# carrier_board.net
KiCad netlist of a schematic drawn in EAGLE
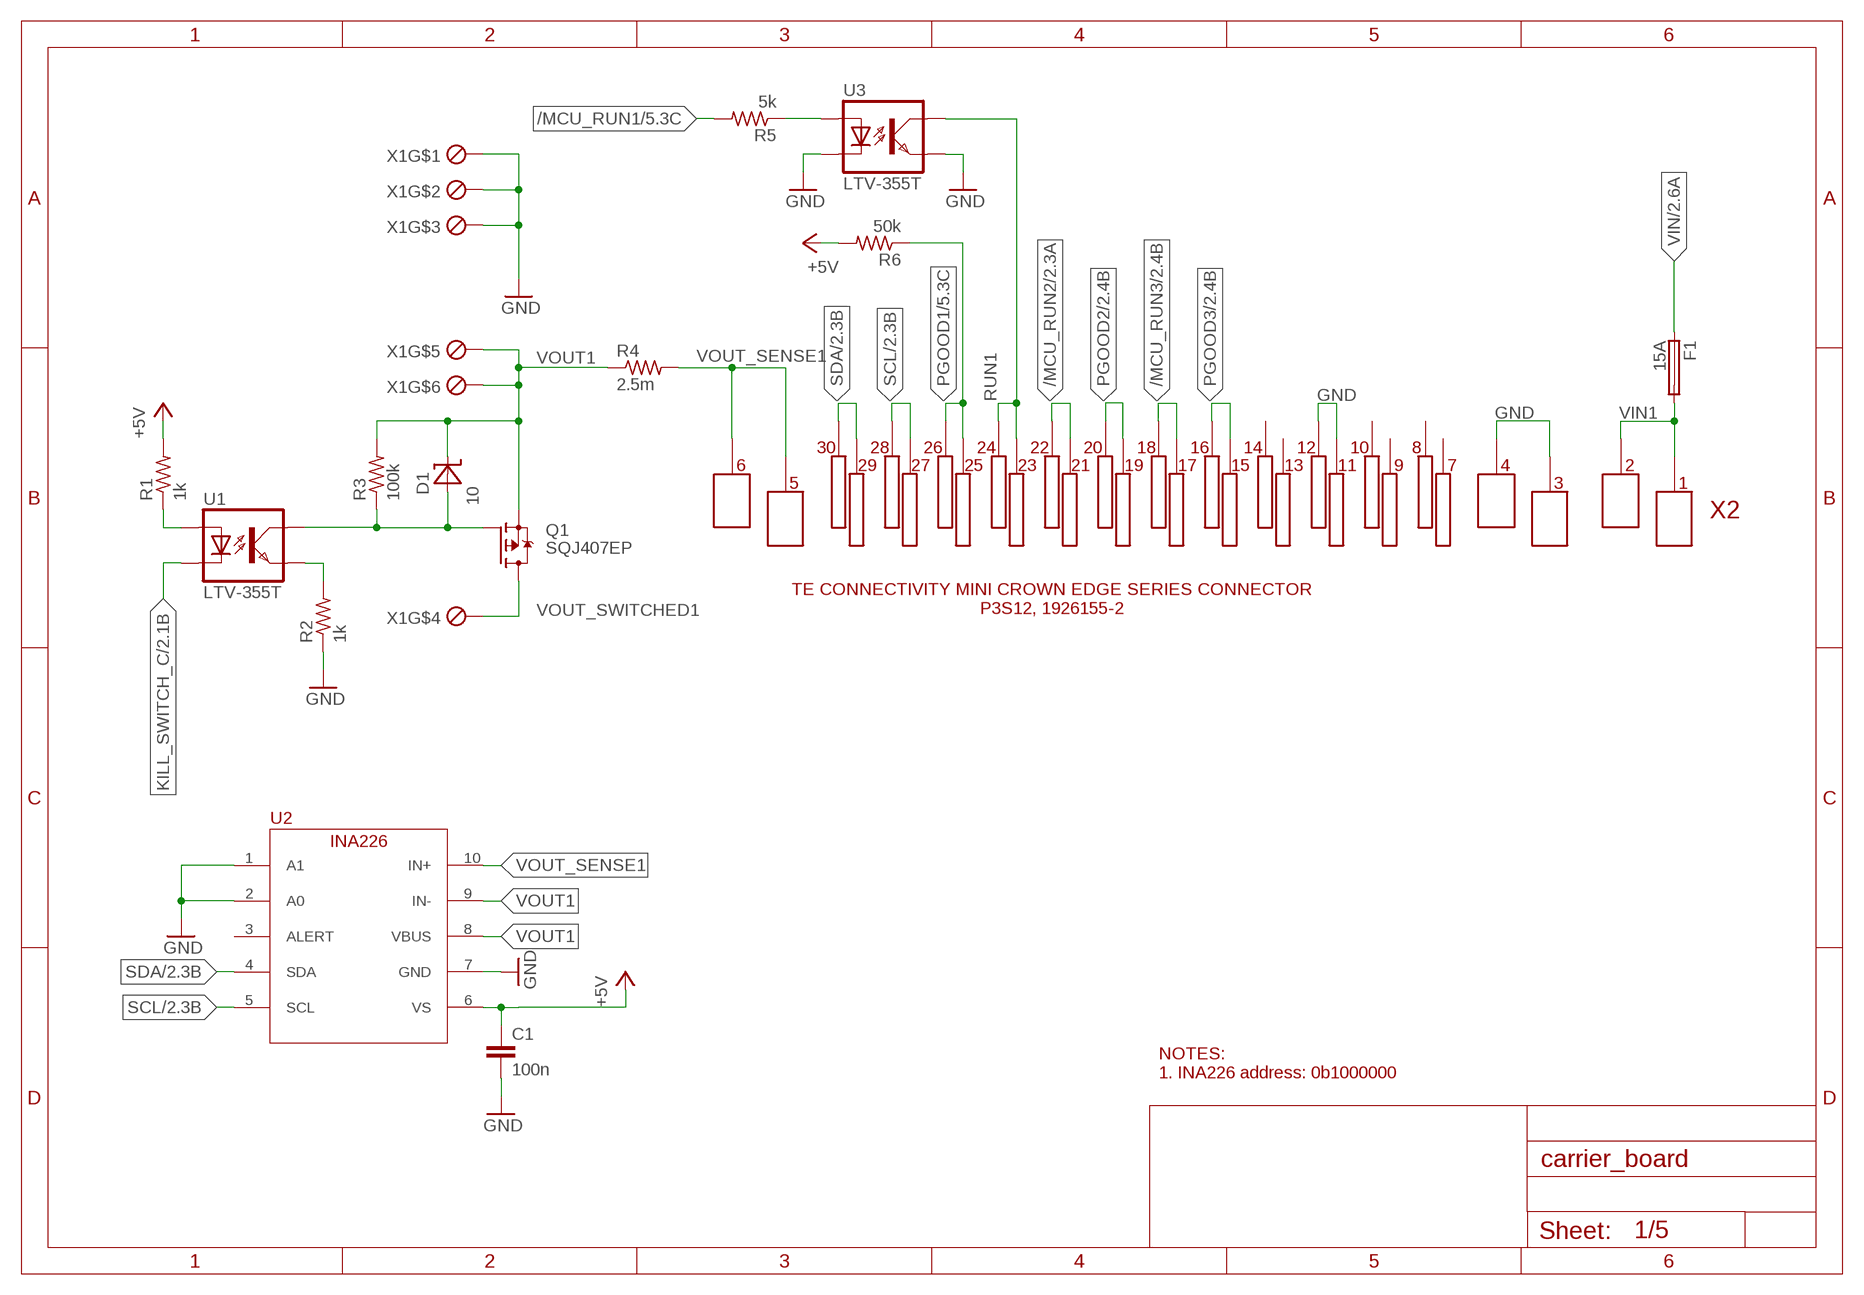
[diagram p0: schematic, sheet 1]
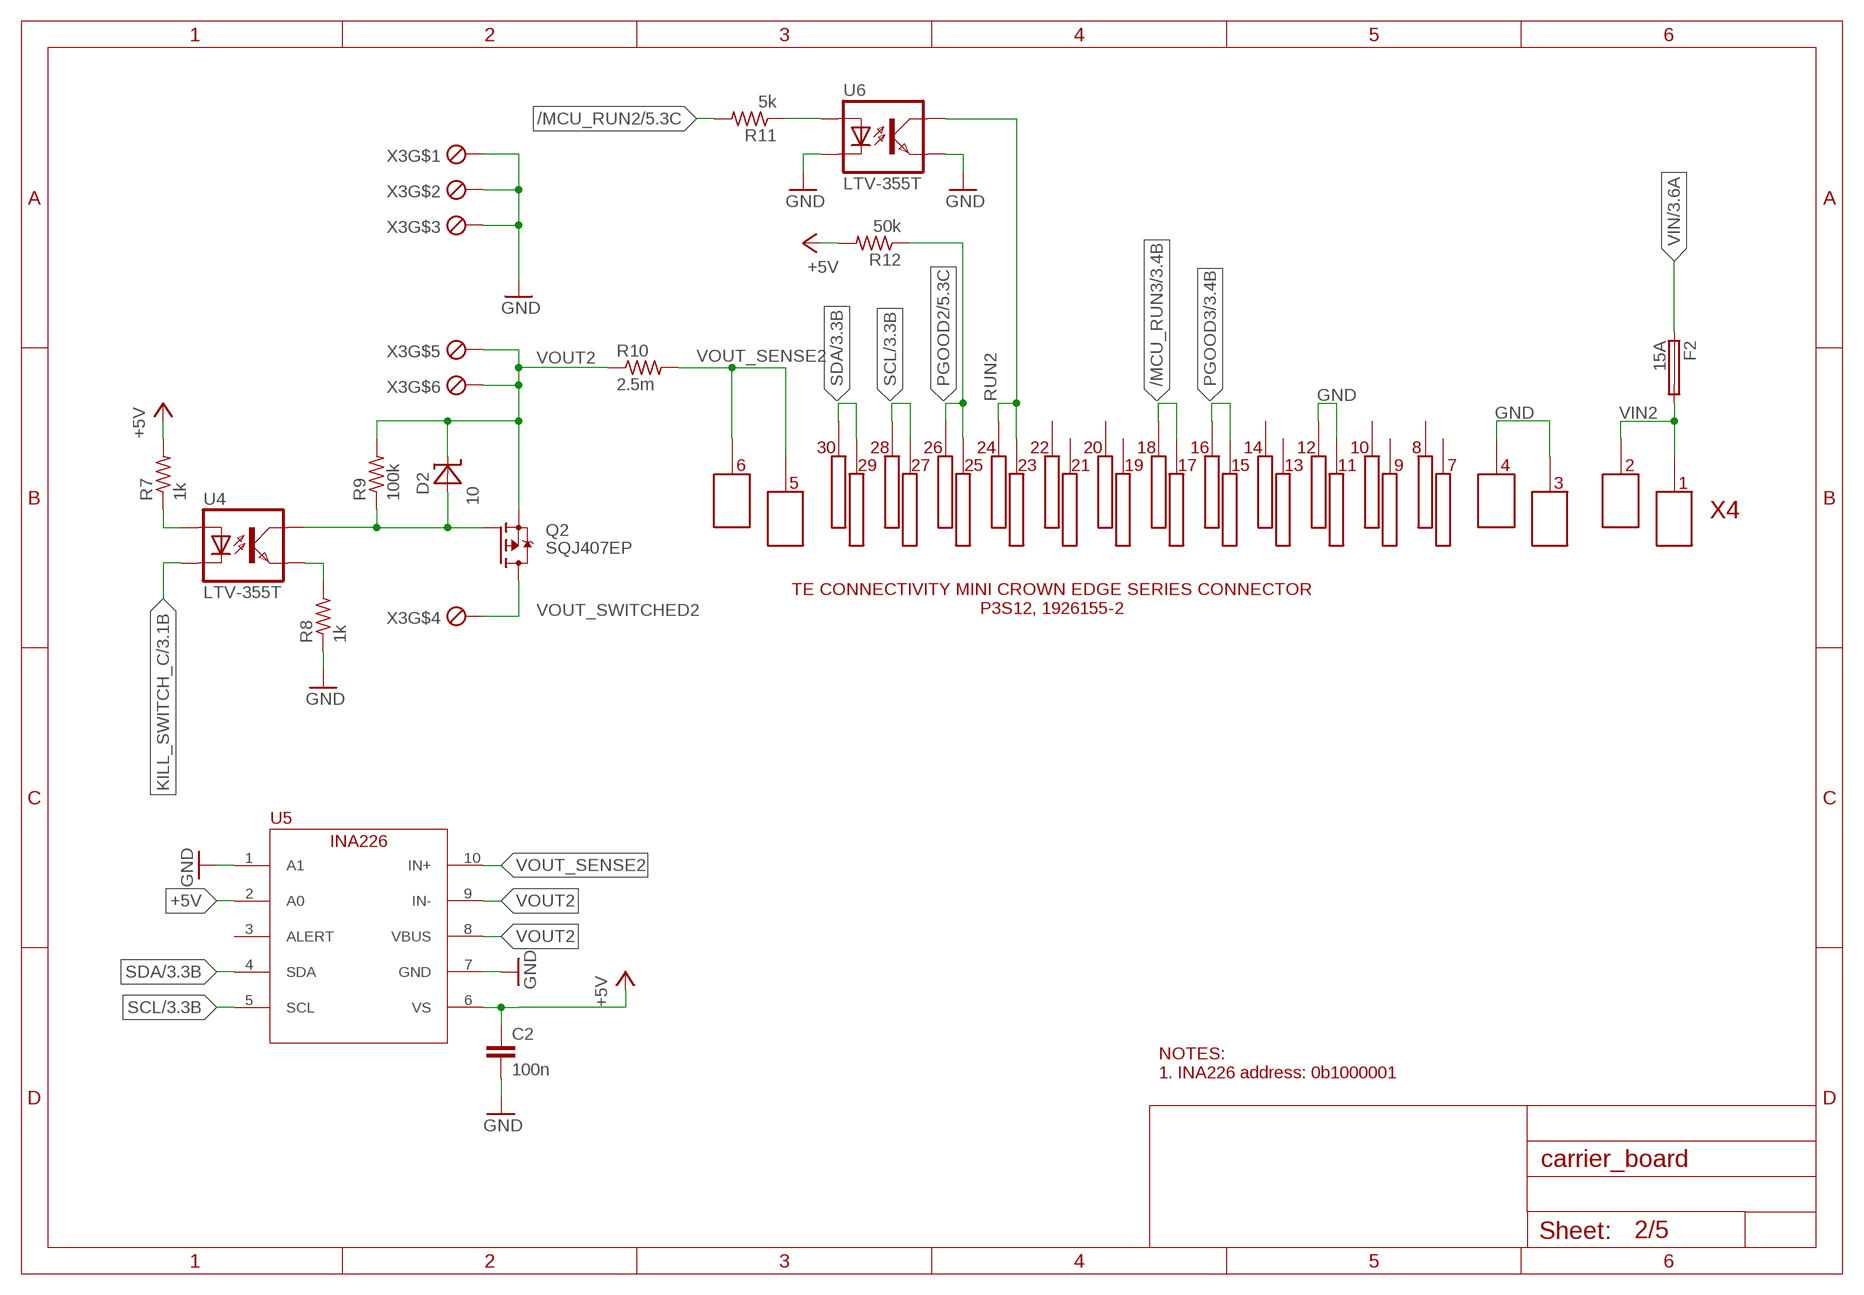
[diagram p1: schematic, sheet 2]
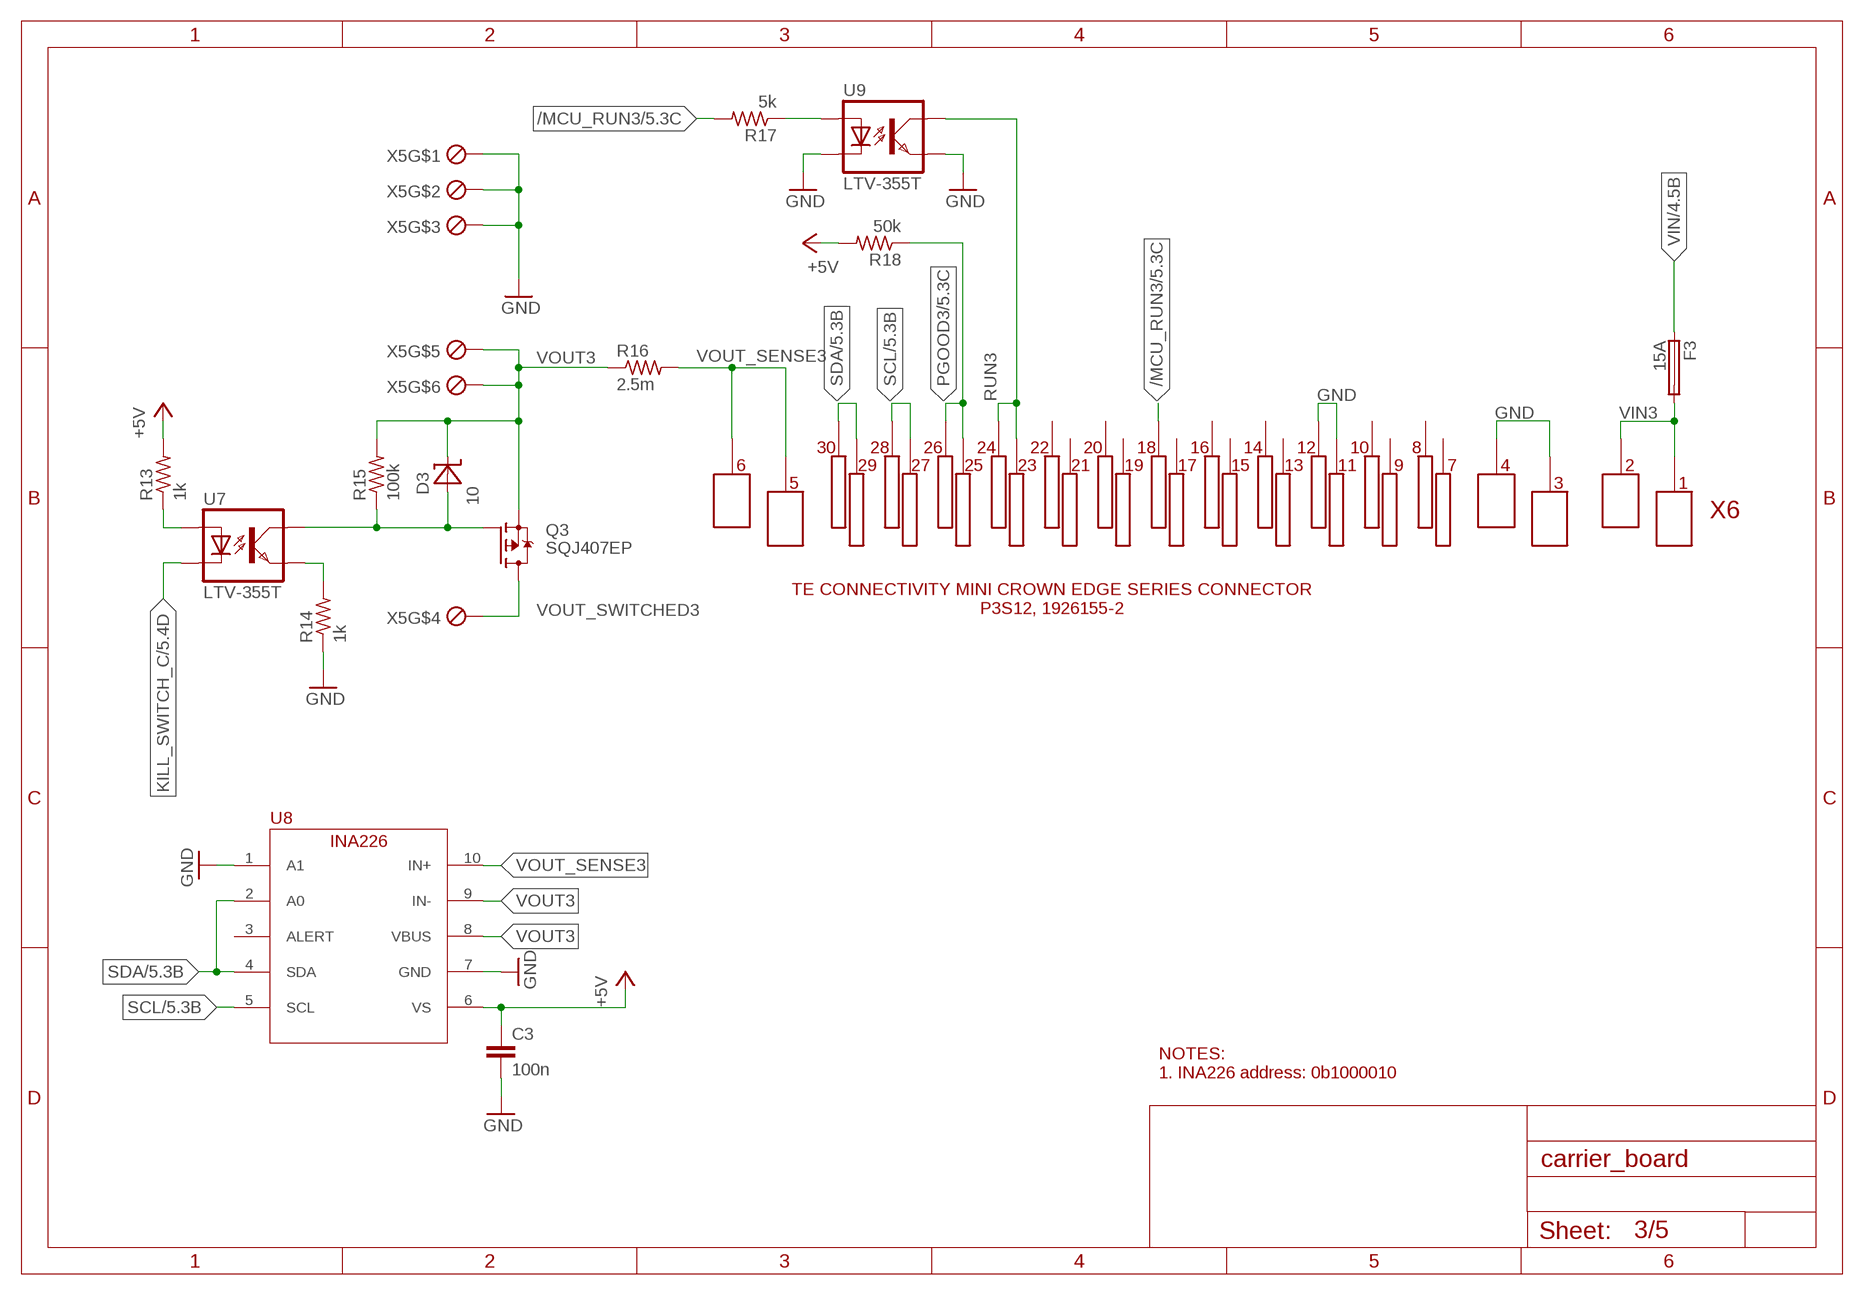
[diagram p2: schematic, sheet 3]
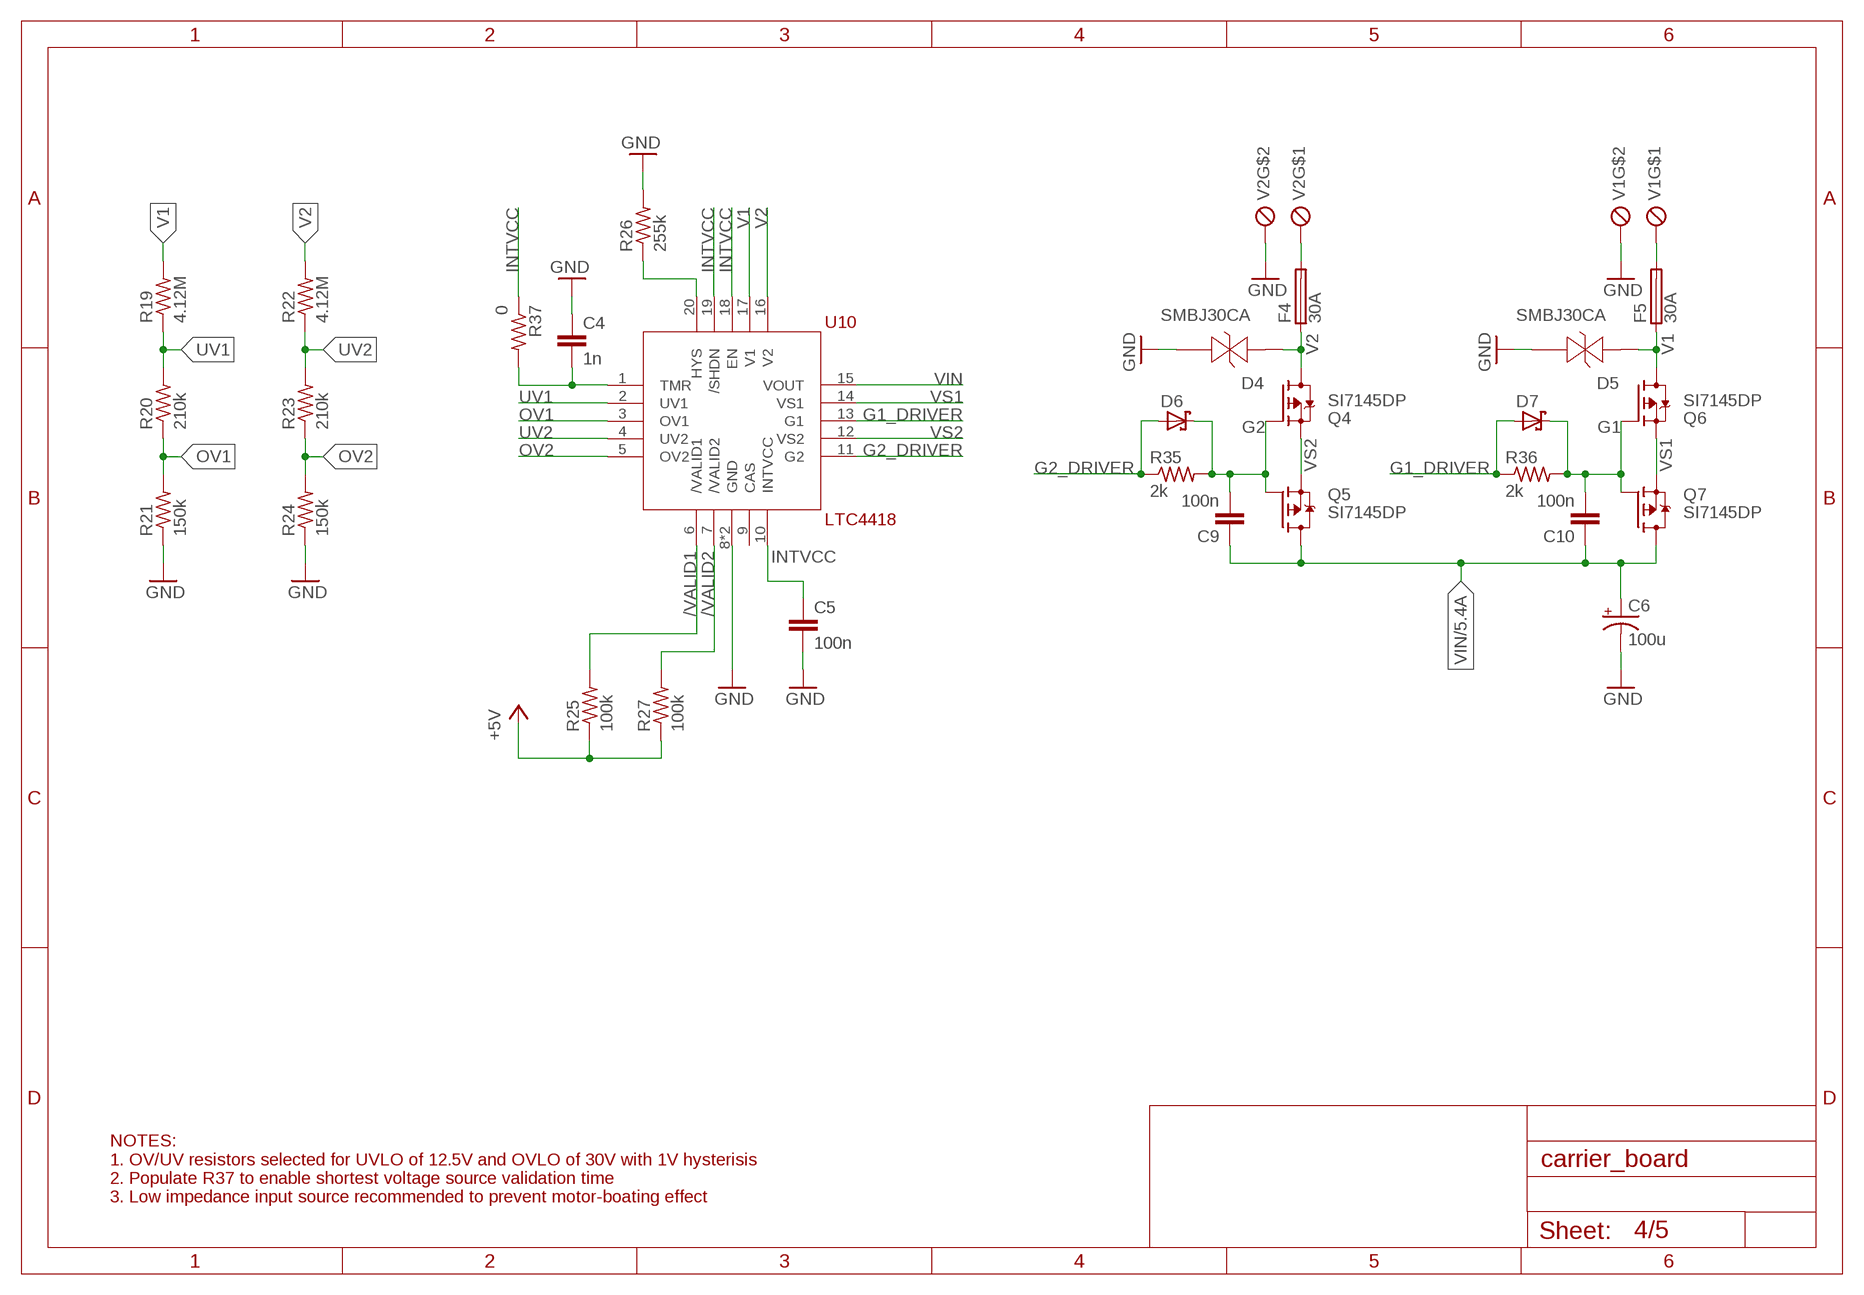
[diagram p3: schematic, sheet 4]
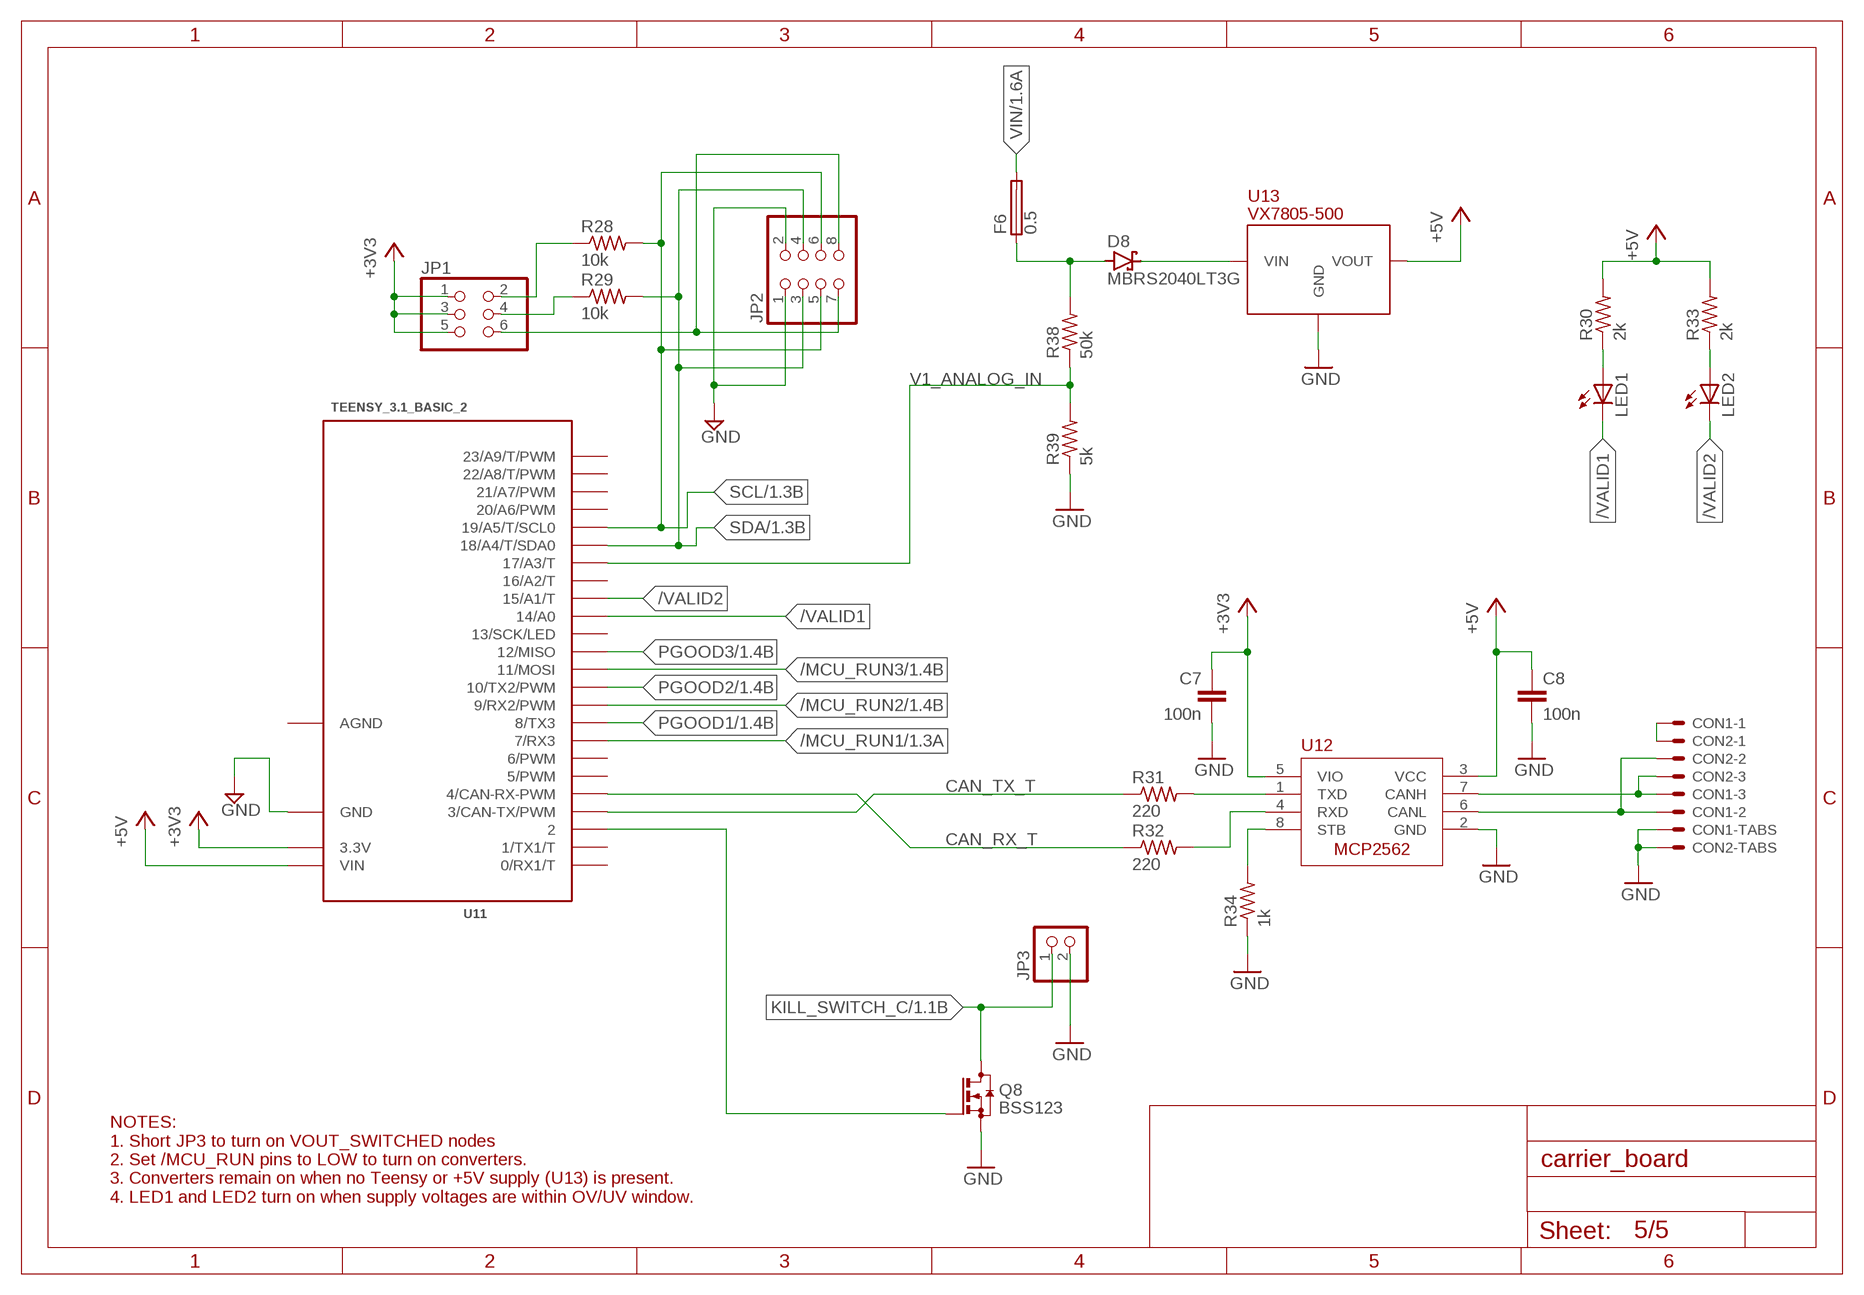
[diagram p4: schematic, sheet 5]

(export (version "E")
  (design (tool "Eeschema 10.0.6"))
  (components
    (comp (ref "C2")
      (value "100n")
      (footprint "eagle-import:C0603")
      (libsource (lib "eagle-import") (part "C-EUC0603"))
    )
    (comp (ref "D2")
      (value "10")
      (footprint "eagle-import:SOD123")
      (libsource (lib "eagle-import") (part "BZT52C10-TP"))
    )
    (comp (ref "F2")
      (value "15A")
      (footprint "eagle-import:3557-10")
      (libsource (lib "eagle-import") (part "3557-10"))
    )
    (comp (ref "Q2")
      (value "SQJ407EP")
      (footprint "eagle-import:POWERPAK_SO8L_SINGLE")
      (libsource (lib "eagle-import") (part "SQJ407EP"))
    )
    (comp (ref "R7")
      (value "1k")
      (footprint "eagle-import:R0603")
      (libsource (lib "eagle-import") (part "R-US_R0603"))
    )
    (comp (ref "R8")
      (value "1k")
      (footprint "eagle-import:R0603")
      (libsource (lib "eagle-import") (part "R-US_R0603"))
    )
    (comp (ref "R9")
      (value "100k")
      (footprint "eagle-import:R0603")
      (libsource (lib "eagle-import") (part "R-US_R0603"))
    )
    (comp (ref "R10")
      (value "2.5m")
      (footprint "eagle-import:R2512")
      (libsource (lib "eagle-import") (part "R-US_R2512"))
    )
    (comp (ref "R11")
      (value "5k")
      (footprint "eagle-import:R0603")
      (libsource (lib "eagle-import") (part "R-US_R0603"))
    )
    (comp (ref "R12")
      (value "50k")
      (footprint "eagle-import:R0603")
      (libsource (lib "eagle-import") (part "R-US_R0603"))
    )
    (comp (ref "U4")
      (value "LTV-355T")
      (footprint "eagle-import:SMD4")
      (libsource (lib "eagle-import") (part "LTV-355T"))
    )
    (comp (ref "U5")
      (value "INA226")
      (footprint "eagle-import:MSOP10")
      (libsource (lib "eagle-import") (part "INA226"))
    )
    (comp (ref "U6")
      (value "LTV-355T")
      (footprint "eagle-import:SMD4")
      (libsource (lib "eagle-import") (part "LTV-355T"))
    )
    (comp (ref "X3")
      (value "284391-6")
      (footprint "eagle-import:284391-6")
      (libsource (lib "eagle-import") (part "284391-6"))
    )
    (comp (ref "X4")
      (value "1926155-2_SOCK")
      (footprint "eagle-import:1926155-2_SOCK")
      (libsource (lib "eagle-import") (part "1926155-2_SOCK"))
    )
    (comp (ref "C4")
      (value "1n")
      (footprint "eagle-import:C0402")
      (libsource (lib "eagle-import") (part "C-EUC0402"))
    )
    (comp (ref "C5")
      (value "100n")
      (footprint "eagle-import:C0402")
      (libsource (lib "eagle-import") (part "C-EUC0402"))
    )
    (comp (ref "C6")
      (value "100u")
      (footprint "eagle-import:E5-10,5")
      (libsource (lib "eagle-import") (part "CPOL-USE5-10.5"))
    )
    (comp (ref "C9")
      (value "100n")
      (footprint "eagle-import:C0603")
      (libsource (lib "eagle-import") (part "C-EUC0603"))
    )
    (comp (ref "C10")
      (value "100n")
      (footprint "eagle-import:C0603")
      (libsource (lib "eagle-import") (part "C-EUC0603"))
    )
    (comp (ref "D4")
      (value "SMBJ30CA")
      (footprint "eagle-import:DO214AA")
      (libsource (lib "eagle-import") (part "SMBJ30CA"))
    )
    (comp (ref "D5")
      (value "SMBJ30CA")
      (footprint "eagle-import:DO214AA")
      (libsource (lib "eagle-import") (part "SMBJ30CA"))
    )
    (comp (ref "D6")
      (value "SD0603S040S0R2")
      (footprint "eagle-import:CHIPLED_0603")
      (libsource (lib "eagle-import") (part "SD0603S040S0R2"))
    )
    (comp (ref "D7")
      (value "SD0603S040S0R2")
      (footprint "eagle-import:CHIPLED_0603")
      (libsource (lib "eagle-import") (part "SD0603S040S0R2"))
    )
    (comp (ref "F4")
      (value "30A")
      (footprint "eagle-import:3557-10")
      (libsource (lib "eagle-import") (part "3557-10"))
    )
    (comp (ref "F5")
      (value "30A")
      (footprint "eagle-import:3557-10")
      (libsource (lib "eagle-import") (part "3557-10"))
    )
    (comp (ref "Q4")
      (value "SI7145DP")
      (footprint "eagle-import:SO-8-POWERPAK")
      (libsource (lib "eagle-import") (part "SI7145"))
    )
    (comp (ref "Q5")
      (value "SI7145DP")
      (footprint "eagle-import:SO-8-POWERPAK")
      (libsource (lib "eagle-import") (part "SI7145"))
    )
    (comp (ref "Q6")
      (value "SI7145DP")
      (footprint "eagle-import:SO-8-POWERPAK")
      (libsource (lib "eagle-import") (part "SI7145"))
    )
    (comp (ref "Q7")
      (value "SI7145DP")
      (footprint "eagle-import:SO-8-POWERPAK")
      (libsource (lib "eagle-import") (part "SI7145"))
    )
    (comp (ref "R19")
      (value "4.12M")
      (footprint "eagle-import:R0402")
      (libsource (lib "eagle-import") (part "R-US_R0402"))
    )
    (comp (ref "R20")
      (value "210k")
      (footprint "eagle-import:R0402")
      (libsource (lib "eagle-import") (part "R-US_R0402"))
    )
    (comp (ref "R21")
      (value "150k")
      (footprint "eagle-import:R0402")
      (libsource (lib "eagle-import") (part "R-US_R0402"))
    )
    (comp (ref "R22")
      (value "4.12M")
      (footprint "eagle-import:R0402")
      (libsource (lib "eagle-import") (part "R-US_R0402"))
    )
    (comp (ref "R23")
      (value "210k")
      (footprint "eagle-import:R0402")
      (libsource (lib "eagle-import") (part "R-US_R0402"))
    )
    (comp (ref "R24")
      (value "150k")
      (footprint "eagle-import:R0402")
      (libsource (lib "eagle-import") (part "R-US_R0402"))
    )
    (comp (ref "R25")
      (value "100k")
      (footprint "eagle-import:R0603")
      (libsource (lib "eagle-import") (part "R-US_R0603"))
    )
    (comp (ref "R26")
      (value "255k")
      (footprint "eagle-import:R0402")
      (libsource (lib "eagle-import") (part "R-US_R0402"))
    )
    (comp (ref "R27")
      (value "100k")
      (footprint "eagle-import:R0603")
      (libsource (lib "eagle-import") (part "R-US_R0603"))
    )
    (comp (ref "R35")
      (value "2k")
      (footprint "eagle-import:R0603")
      (libsource (lib "eagle-import") (part "R-US_R0603"))
    )
    (comp (ref "R36")
      (value "2k")
      (footprint "eagle-import:R0603")
      (libsource (lib "eagle-import") (part "R-US_R0603"))
    )
    (comp (ref "R37")
      (value "0")
      (footprint "eagle-import:R0402")
      (libsource (lib "eagle-import") (part "R-US_R0402"))
    )
    (comp (ref "U10")
      (value "LTC4418")
      (footprint "eagle-import:QFN20")
      (libsource (lib "eagle-import") (part "LTC4418"))
    )
    (comp (ref "V1")
      (value "MKDSD_1730502")
      (footprint "eagle-import:MKDSD_1730502")
      (libsource (lib "eagle-import") (part "MKDSD_1730502"))
    )
    (comp (ref "V2")
      (value "MKDSD_1730502")
      (footprint "eagle-import:MKDSD_1730502")
      (libsource (lib "eagle-import") (part "MKDSD_1730502"))
    )
    (comp (ref "C3")
      (value "100n")
      (footprint "eagle-import:C0603")
      (libsource (lib "eagle-import") (part "C-EUC0603"))
    )
    (comp (ref "D3")
      (value "10")
      (footprint "eagle-import:SOD123")
      (libsource (lib "eagle-import") (part "BZT52C10-TP"))
    )
    (comp (ref "F3")
      (value "15A")
      (footprint "eagle-import:3557-10")
      (libsource (lib "eagle-import") (part "3557-10"))
    )
    (comp (ref "Q3")
      (value "SQJ407EP")
      (footprint "eagle-import:POWERPAK_SO8L_SINGLE")
      (libsource (lib "eagle-import") (part "SQJ407EP"))
    )
    (comp (ref "R13")
      (value "1k")
      (footprint "eagle-import:R0603")
      (libsource (lib "eagle-import") (part "R-US_R0603"))
    )
    (comp (ref "R14")
      (value "1k")
      (footprint "eagle-import:R0603")
      (libsource (lib "eagle-import") (part "R-US_R0603"))
    )
    (comp (ref "R15")
      (value "100k")
      (footprint "eagle-import:R0603")
      (libsource (lib "eagle-import") (part "R-US_R0603"))
    )
    (comp (ref "R16")
      (value "2.5m")
      (footprint "eagle-import:R2512")
      (libsource (lib "eagle-import") (part "R-US_R2512"))
    )
    (comp (ref "R17")
      (value "5k")
      (footprint "eagle-import:R0603")
      (libsource (lib "eagle-import") (part "R-US_R0603"))
    )
    (comp (ref "R18")
      (value "50k")
      (footprint "eagle-import:R0603")
      (libsource (lib "eagle-import") (part "R-US_R0603"))
    )
    (comp (ref "U7")
      (value "LTV-355T")
      (footprint "eagle-import:SMD4")
      (libsource (lib "eagle-import") (part "LTV-355T"))
    )
    (comp (ref "U8")
      (value "INA226")
      (footprint "eagle-import:MSOP10")
      (libsource (lib "eagle-import") (part "INA226"))
    )
    (comp (ref "U9")
      (value "LTV-355T")
      (footprint "eagle-import:SMD4")
      (libsource (lib "eagle-import") (part "LTV-355T"))
    )
    (comp (ref "X5")
      (value "284391-6")
      (footprint "eagle-import:284391-6")
      (libsource (lib "eagle-import") (part "284391-6"))
    )
    (comp (ref "X6")
      (value "1926155-2_SOCK")
      (footprint "eagle-import:1926155-2_SOCK")
      (libsource (lib "eagle-import") (part "1926155-2_SOCK"))
    )
    (comp (ref "C1")
      (value "100n")
      (footprint "eagle-import:C0603")
      (libsource (lib "eagle-import") (part "C-EUC0603"))
    )
    (comp (ref "D1")
      (value "10")
      (footprint "eagle-import:SOD123")
      (libsource (lib "eagle-import") (part "BZT52C10-TP"))
    )
    (comp (ref "F1")
      (value "15A")
      (footprint "eagle-import:3557-10")
      (libsource (lib "eagle-import") (part "3557-10"))
    )
    (comp (ref "Q1")
      (value "SQJ407EP")
      (footprint "eagle-import:POWERPAK_SO8L_SINGLE")
      (libsource (lib "eagle-import") (part "SQJ407EP"))
    )
    (comp (ref "R1")
      (value "1k")
      (footprint "eagle-import:R0603")
      (libsource (lib "eagle-import") (part "R-US_R0603"))
    )
    (comp (ref "R2")
      (value "1k")
      (footprint "eagle-import:R0603")
      (libsource (lib "eagle-import") (part "R-US_R0603"))
    )
    (comp (ref "R3")
      (value "100k")
      (footprint "eagle-import:R0603")
      (libsource (lib "eagle-import") (part "R-US_R0603"))
    )
    (comp (ref "R4")
      (value "2.5m")
      (footprint "eagle-import:R2512")
      (libsource (lib "eagle-import") (part "R-US_R2512"))
    )
    (comp (ref "R5")
      (value "5k")
      (footprint "eagle-import:R0603")
      (libsource (lib "eagle-import") (part "R-US_R0603"))
    )
    (comp (ref "R6")
      (value "50k")
      (footprint "eagle-import:R0603")
      (libsource (lib "eagle-import") (part "R-US_R0603"))
    )
    (comp (ref "U1")
      (value "LTV-355T")
      (footprint "eagle-import:SMD4")
      (libsource (lib "eagle-import") (part "LTV-355T"))
    )
    (comp (ref "U2")
      (value "INA226")
      (footprint "eagle-import:MSOP10")
      (libsource (lib "eagle-import") (part "INA226"))
    )
    (comp (ref "U3")
      (value "LTV-355T")
      (footprint "eagle-import:SMD4")
      (libsource (lib "eagle-import") (part "LTV-355T"))
    )
    (comp (ref "X1")
      (value "284391-6")
      (footprint "eagle-import:284391-6")
      (libsource (lib "eagle-import") (part "284391-6"))
    )
    (comp (ref "X2")
      (value "1926155-2_SOCK")
      (footprint "eagle-import:1926155-2_SOCK")
      (libsource (lib "eagle-import") (part "1926155-2_SOCK"))
    )
    (comp (ref "C7")
      (value "100n")
      (footprint "eagle-import:C0805")
      (libsource (lib "eagle-import") (part "C-EUC0805"))
    )
    (comp (ref "C8")
      (value "100n")
      (footprint "eagle-import:C0805")
      (libsource (lib "eagle-import") (part "C-EUC0805"))
    )
    (comp (ref "CON1")
      (value "SM03B-GHS-TB")
      (footprint "eagle-import:SM03B-GHS-TB")
      (libsource (lib "eagle-import") (part "SM03B-GHS-TB"))
    )
    (comp (ref "CON2")
      (value "SM03B-GHS-TB")
      (footprint "eagle-import:SM03B-GHS-TB")
      (libsource (lib "eagle-import") (part "SM03B-GHS-TB"))
    )
    (comp (ref "D8")
      (value "MBRS2040LT3G")
      (footprint "eagle-import:SMB")
      (libsource (lib "eagle-import") (part "MBRS130LT3"))
    )
    (comp (ref "F6")
      (value "0.5")
      (footprint "eagle-import:R1206")
      (libsource (lib "eagle-import") (part "501_FUSE"))
    )
    (comp (ref "JP1")
      (value "PINHD-2X3")
      (footprint "eagle-import:2X03")
      (libsource (lib "eagle-import") (part "PINHD-2X3"))
    )
    (comp (ref "JP2")
      (value "PINHD-2X4")
      (footprint "eagle-import:2X04")
      (libsource (lib "eagle-import") (part "PINHD-2X4"))
    )
    (comp (ref "JP3")
      (value "PINHD-1X02_2.54-SMD-90°")
      (footprint "eagle-import:1X02SMD_90")
      (libsource (lib "eagle-import") (part "PINHD-1X02_2.54-SMD-90°"))
    )
    (comp (ref "LED1")
      (value "LEDCHIPLED_0603")
      (footprint "eagle-import:CHIPLED_0603")
      (libsource (lib "eagle-import") (part "LEDCHIPLED_0603"))
    )
    (comp (ref "LED2")
      (value "LEDCHIPLED_0603")
      (footprint "eagle-import:CHIPLED_0603")
      (libsource (lib "eagle-import") (part "LEDCHIPLED_0603"))
    )
    (comp (ref "Q8")
      (value "BSS123")
      (footprint "eagle-import:SOT23")
      (libsource (lib "eagle-import") (part "BSS123"))
    )
    (comp (ref "R28")
      (value "10k")
      (footprint "eagle-import:R0805")
      (libsource (lib "eagle-import") (part "R-US_R0805"))
    )
    (comp (ref "R29")
      (value "10k")
      (footprint "eagle-import:R0805")
      (libsource (lib "eagle-import") (part "R-US_R0805"))
    )
    (comp (ref "R30")
      (value "2k")
      (footprint "eagle-import:R0603")
      (libsource (lib "eagle-import") (part "R-US_R0603"))
    )
    (comp (ref "R31")
      (value "220")
      (footprint "eagle-import:R0805")
      (libsource (lib "eagle-import") (part "R-US_R0805"))
    )
    (comp (ref "R32")
      (value "220")
      (footprint "eagle-import:R0805")
      (libsource (lib "eagle-import") (part "R-US_R0805"))
    )
    (comp (ref "R33")
      (value "2k")
      (footprint "eagle-import:R0603")
      (libsource (lib "eagle-import") (part "R-US_R0603"))
    )
    (comp (ref "R34")
      (value "1k")
      (footprint "eagle-import:R0805")
      (libsource (lib "eagle-import") (part "R-US_R0805"))
    )
    (comp (ref "R38")
      (value "50k")
      (footprint "eagle-import:R0603")
      (libsource (lib "eagle-import") (part "R-US_R0603"))
    )
    (comp (ref "R39")
      (value "5k")
      (footprint "eagle-import:R0603")
      (libsource (lib "eagle-import") (part "R-US_R0603"))
    )
    (comp (ref "U11")
      (value "TEENSY_3.1_BASIC_2")
      (footprint "eagle-import:TEENSY_3.1_BASIC_2")
      (libsource (lib "eagle-import") (part "TEENSY_3.1_BASIC_2"))
    )
    (comp (ref "U12")
      (value "MCP2562")
      (footprint "eagle-import:SO-8")
      (libsource (lib "eagle-import") (part "MCP2562"))
    )
    (comp (ref "U13")
      (value "VX7805-500")
      (footprint "eagle-import:0.1__LINEAR_REGULATOR_REPLACEMENT")
      (libsource (lib "eagle-import") (part "0.1{dblquote}_LINEAR_REGULATOR_REPLACEMENT"))
    )
  )
  (nets
    (net (code "1") (name "+3V3") (class "Default")
      (node (ref "C7") (pin "1") (pinfunction "1_1") (pintype "passive"))
      (node (ref "JP1") (pin "1") (pinfunction "1_1") (pintype "passive"))
      (node (ref "JP1") (pin "3") (pinfunction "3_3") (pintype "passive"))
      (node (ref "JP1") (pin "5") (pinfunction "5_5") (pintype "passive"))
      (node (ref "U11") (pin "3.3V") (pinfunction "3.3V_3.3V") (pintype "power_in"))
      (node (ref "U12") (pin "5") (pinfunction "VIO_5") (pintype "bidirectional"))
    )
    (net (code "2") (name "+5V") (class "Default")
      (node (ref "C1") (pin "1") (pinfunction "1_1") (pintype "passive"))
      (node (ref "C2") (pin "1") (pinfunction "1_1") (pintype "passive"))
      (node (ref "C3") (pin "1") (pinfunction "1_1") (pintype "passive"))
      (node (ref "C8") (pin "1") (pinfunction "1_1") (pintype "passive"))
      (node (ref "R1") (pin "2") (pinfunction "2_2") (pintype "passive"))
      (node (ref "R12") (pin "2") (pinfunction "2_2") (pintype "passive"))
      (node (ref "R13") (pin "2") (pinfunction "2_2") (pintype "passive"))
      (node (ref "R18") (pin "2") (pinfunction "2_2") (pintype "passive"))
      (node (ref "R25") (pin "1") (pinfunction "1_1") (pintype "passive"))
      (node (ref "R27") (pin "1") (pinfunction "1_1") (pintype "passive"))
      (node (ref "R30") (pin "2") (pinfunction "2_2") (pintype "passive"))
      (node (ref "R33") (pin "2") (pinfunction "2_2") (pintype "passive"))
      (node (ref "R6") (pin "2") (pinfunction "2_2") (pintype "passive"))
      (node (ref "R7") (pin "2") (pinfunction "2_2") (pintype "passive"))
      (node (ref "U11") (pin "VIN") (pinfunction "VIN_VIN") (pintype "power_in"))
      (node (ref "U12") (pin "3") (pinfunction "VCC_3") (pintype "bidirectional"))
      (node (ref "U13") (pin "3") (pinfunction "VOUT_3") (pintype "passive"))
      (node (ref "U2") (pin "6") (pinfunction "VS_6") (pintype "bidirectional"))
      (node (ref "U5") (pin "2") (pinfunction "A0_2") (pintype "bidirectional"))
      (node (ref "U5") (pin "6") (pinfunction "VS_6") (pintype "bidirectional"))
      (node (ref "U8") (pin "6") (pinfunction "VS_6") (pintype "bidirectional"))
    )
    (net (code "3") (name "AGND") (class "Default")
      (node (ref "U11") (pin "AGND") (pinfunction "AGND_AGND") (pintype "power_in"))
    )
    (net (code "4") (name "CAN_RX_T") (class "Default")
      (node (ref "R32") (pin "1") (pinfunction "1_1") (pintype "passive"))
      (node (ref "U11") (pin "4") (pinfunction "4/CAN-RX-PWM_4") (pintype "bidirectional"))
    )
    (net (code "5") (name "CAN_TX_T") (class "Default")
      (node (ref "R31") (pin "1") (pinfunction "1_1") (pintype "passive"))
      (node (ref "U11") (pin "3") (pinfunction "3/CAN-TX/PWM_3") (pintype "bidirectional"))
    )
    (net (code "6") (name "G1") (class "Default")
      (node (ref "C10") (pin "2") (pinfunction "2_2") (pintype "passive"))
      (node (ref "D7") (pin "C") (pinfunction "C_C") (pintype "passive"))
      (node (ref "Q6") (pin "4") (pinfunction "G_4") (pintype "passive"))
      (node (ref "Q7") (pin "4") (pinfunction "G_4") (pintype "passive"))
      (node (ref "R36") (pin "2") (pinfunction "2_2") (pintype "passive"))
    )
    (net (code "7") (name "G1_DRIVER") (class "Default")
      (node (ref "D7") (pin "A") (pinfunction "A_A") (pintype "passive"))
      (node (ref "R36") (pin "1") (pinfunction "1_1") (pintype "passive"))
      (node (ref "U10") (pin "13") (pinfunction "G1_13") (pintype "bidirectional"))
    )
    (net (code "8") (name "G2") (class "Default")
      (node (ref "C9") (pin "2") (pinfunction "2_2") (pintype "passive"))
      (node (ref "D6") (pin "C") (pinfunction "C_C") (pintype "passive"))
      (node (ref "Q4") (pin "4") (pinfunction "G_4") (pintype "passive"))
      (node (ref "Q5") (pin "4") (pinfunction "G_4") (pintype "passive"))
      (node (ref "R35") (pin "2") (pinfunction "2_2") (pintype "passive"))
    )
    (net (code "9") (name "G2_DRIVER") (class "Default")
      (node (ref "D6") (pin "A") (pinfunction "A_A") (pintype "passive"))
      (node (ref "R35") (pin "1") (pinfunction "1_1") (pintype "passive"))
      (node (ref "U10") (pin "11") (pinfunction "G2_11") (pintype "bidirectional"))
    )
    (net (code "10") (name "GND") (class "Default")
      (node (ref "C1") (pin "2") (pinfunction "2_2") (pintype "passive"))
      (node (ref "C2") (pin "2") (pinfunction "2_2") (pintype "passive"))
      (node (ref "C3") (pin "2") (pinfunction "2_2") (pintype "passive"))
      (node (ref "C4") (pin "1") (pinfunction "1_1") (pintype "passive"))
      (node (ref "C5") (pin "2") (pinfunction "2_2") (pintype "passive"))
      (node (ref "C6") (pin "-") (pinfunction "-_-") (pintype "passive"))
      (node (ref "C7") (pin "2") (pinfunction "2_2") (pintype "passive"))
      (node (ref "C8") (pin "2") (pinfunction "2_2") (pintype "passive"))
      (node (ref "CON1") (pin "P$4") (pinfunction "S_P$4") (pintype "passive"))
      (node (ref "CON1") (pin "P$5") (pinfunction "S_P$5") (pintype "passive"))
      (node (ref "CON2") (pin "P$4") (pinfunction "S_P$4") (pintype "passive"))
      (node (ref "CON2") (pin "P$5") (pinfunction "S_P$5") (pintype "passive"))
      (node (ref "D4") (pin "A") (pinfunction "2_A") (pintype "passive"))
      (node (ref "D5") (pin "A") (pinfunction "2_A") (pintype "passive"))
      (node (ref "JP2") (pin "1") (pinfunction "1_1") (pintype "passive"))
      (node (ref "JP2") (pin "2") (pinfunction "2_2") (pintype "passive"))
      (node (ref "JP3") (pin "2") (pinfunction "2_2") (pintype "passive"))
      (node (ref "Q8") (pin "2") (pinfunction "S_2") (pintype "passive"))
      (node (ref "R14") (pin "1") (pinfunction "1_1") (pintype "passive"))
      (node (ref "R2") (pin "1") (pinfunction "1_1") (pintype "passive"))
      (node (ref "R21") (pin "1") (pinfunction "1_1") (pintype "passive"))
      (node (ref "R24") (pin "1") (pinfunction "1_1") (pintype "passive"))
      (node (ref "R26") (pin "2") (pinfunction "2_2") (pintype "passive"))
      (node (ref "R34") (pin "1") (pinfunction "1_1") (pintype "passive"))
      (node (ref "R39") (pin "1") (pinfunction "1_1") (pintype "passive"))
      (node (ref "R8") (pin "1") (pinfunction "1_1") (pintype "passive"))
      (node (ref "U10") (pin "8") (pinfunction "GND_8") (pintype "bidirectional"))
      (node (ref "U10") (pin "EXP") (pinfunction "GND_EXP") (pintype "bidirectional"))
      (node (ref "U11") (pin "GND") (pinfunction "GND_GND") (pintype "power_in"))
      (node (ref "U12") (pin "2") (pinfunction "GND_2") (pintype "bidirectional"))
      (node (ref "U13") (pin "2") (pinfunction "GND_2") (pintype "passive"))
      (node (ref "U2") (pin "1") (pinfunction "A1_1") (pintype "bidirectional"))
      (node (ref "U2") (pin "2") (pinfunction "A0_2") (pintype "bidirectional"))
      (node (ref "U2") (pin "7") (pinfunction "GND_7") (pintype "bidirectional"))
      (node (ref "U3") (pin "CATHODE") (pinfunction "C_CATHODE") (pintype "passive"))
      (node (ref "U3") (pin "EMITTER") (pinfunction "EMIT_EMITTER") (pintype "passive"))
      (node (ref "U5") (pin "1") (pinfunction "A1_1") (pintype "bidirectional"))
      (node (ref "U5") (pin "7") (pinfunction "GND_7") (pintype "bidirectional"))
      (node (ref "U6") (pin "CATHODE") (pinfunction "C_CATHODE") (pintype "passive"))
      (node (ref "U6") (pin "EMITTER") (pinfunction "EMIT_EMITTER") (pintype "passive"))
      (node (ref "U8") (pin "1") (pinfunction "A1_1") (pintype "bidirectional"))
      (node (ref "U8") (pin "7") (pinfunction "GND_7") (pintype "bidirectional"))
      (node (ref "U9") (pin "CATHODE") (pinfunction "C_CATHODE") (pintype "passive"))
      (node (ref "U9") (pin "EMITTER") (pinfunction "EMIT_EMITTER") (pintype "passive"))
      (node (ref "V1") (pin "P$2") (pinfunction "1_P$2") (pintype "passive"))
      (node (ref "V1") (pin "P$4") (pinfunction "1_P$4") (pintype "passive"))
      (node (ref "V2") (pin "P$2") (pinfunction "1_P$2") (pintype "passive"))
      (node (ref "V2") (pin "P$4") (pinfunction "1_P$4") (pintype "passive"))
      (node (ref "X1") (pin "P$1") (pinfunction "1_P$1") (pintype "passive"))
      (node (ref "X1") (pin "P$2") (pinfunction "1_P$2") (pintype "passive"))
      (node (ref "X1") (pin "P$3") (pinfunction "1_P$3") (pintype "passive"))
      (node (ref "X2") (pin "P$11") (pinfunction "P$11_P$11") (pintype "bidirectional"))
      (node (ref "X2") (pin "P$12") (pinfunction "P$12_P$12") (pintype "bidirectional"))
      (node (ref "X2") (pin "P$3_1") (pinfunction "P$3_P$3_1") (pintype "bidirectional"))
      (node (ref "X2") (pin "P$3_2") (pinfunction "P$3_P$3_2") (pintype "bidirectional"))
      (node (ref "X2") (pin "P$3_3") (pinfunction "P$3_P$3_3") (pintype "bidirectional"))
      (node (ref "X2") (pin "P$4_1") (pinfunction "P$4_P$4_1") (pintype "bidirectional"))
      (node (ref "X2") (pin "P$4_2") (pinfunction "P$4_P$4_2") (pintype "bidirectional"))
      (node (ref "X2") (pin "P$4_3") (pinfunction "P$4_P$4_3") (pintype "bidirectional"))
      (node (ref "X3") (pin "P$1") (pinfunction "1_P$1") (pintype "passive"))
      (node (ref "X3") (pin "P$2") (pinfunction "1_P$2") (pintype "passive"))
      (node (ref "X3") (pin "P$3") (pinfunction "1_P$3") (pintype "passive"))
      (node (ref "X4") (pin "P$11") (pinfunction "P$11_P$11") (pintype "bidirectional"))
      (node (ref "X4") (pin "P$12") (pinfunction "P$12_P$12") (pintype "bidirectional"))
      (node (ref "X4") (pin "P$3_1") (pinfunction "P$3_P$3_1") (pintype "bidirectional"))
      (node (ref "X4") (pin "P$3_2") (pinfunction "P$3_P$3_2") (pintype "bidirectional"))
      (node (ref "X4") (pin "P$3_3") (pinfunction "P$3_P$3_3") (pintype "bidirectional"))
      (node (ref "X4") (pin "P$4_1") (pinfunction "P$4_P$4_1") (pintype "bidirectional"))
      (node (ref "X4") (pin "P$4_2") (pinfunction "P$4_P$4_2") (pintype "bidirectional"))
      (node (ref "X4") (pin "P$4_3") (pinfunction "P$4_P$4_3") (pintype "bidirectional"))
      (node (ref "X5") (pin "P$1") (pinfunction "1_P$1") (pintype "passive"))
      (node (ref "X5") (pin "P$2") (pinfunction "1_P$2") (pintype "passive"))
      (node (ref "X5") (pin "P$3") (pinfunction "1_P$3") (pintype "passive"))
      (node (ref "X6") (pin "P$11") (pinfunction "P$11_P$11") (pintype "bidirectional"))
      (node (ref "X6") (pin "P$12") (pinfunction "P$12_P$12") (pintype "bidirectional"))
      (node (ref "X6") (pin "P$3_1") (pinfunction "P$3_P$3_1") (pintype "bidirectional"))
      (node (ref "X6") (pin "P$3_2") (pinfunction "P$3_P$3_2") (pintype "bidirectional"))
      (node (ref "X6") (pin "P$3_3") (pinfunction "P$3_P$3_3") (pintype "bidirectional"))
      (node (ref "X6") (pin "P$4_1") (pinfunction "P$4_P$4_1") (pintype "bidirectional"))
      (node (ref "X6") (pin "P$4_2") (pinfunction "P$4_P$4_2") (pintype "bidirectional"))
      (node (ref "X6") (pin "P$4_3") (pinfunction "P$4_P$4_3") (pintype "bidirectional"))
    )
    (net (code "11") (name "INTVCC") (class "Default")
      (node (ref "C5") (pin "1") (pinfunction "1_1") (pintype "passive"))
      (node (ref "R37") (pin "1") (pinfunction "1_1") (pintype "passive"))
      (node (ref "U10") (pin "10") (pinfunction "INTVCC_10") (pintype "bidirectional"))
      (node (ref "U10") (pin "18") (pinfunction "EN_18") (pintype "bidirectional"))
      (node (ref "U10") (pin "19") (pinfunction "/SHDN_19") (pintype "bidirectional"))
    )
    (net (code "12") (name "KILL_SWITCH_C") (class "Default")
      (node (ref "JP3") (pin "1") (pinfunction "1_1") (pintype "passive"))
      (node (ref "Q8") (pin "3") (pinfunction "D_3") (pintype "passive"))
      (node (ref "U1") (pin "CATHODE") (pinfunction "C_CATHODE") (pintype "passive"))
      (node (ref "U4") (pin "CATHODE") (pinfunction "C_CATHODE") (pintype "passive"))
      (node (ref "U7") (pin "CATHODE") (pinfunction "C_CATHODE") (pintype "passive"))
    )
    (net (code "13") (name "Net-(CON1A-S)") (class "Default")
      (node (ref "CON1") (pin "P$1") (pinfunction "S_P$1") (pintype "passive"))
      (node (ref "CON2") (pin "P$1") (pinfunction "S_P$1") (pintype "passive"))
    )
    (net (code "14") (name "Net-(CON1B-S)") (class "Default")
      (node (ref "CON1") (pin "P$2") (pinfunction "S_P$2") (pintype "passive"))
      (node (ref "CON2") (pin "P$2") (pinfunction "S_P$2") (pintype "passive"))
      (node (ref "U12") (pin "6") (pinfunction "CANL_6") (pintype "bidirectional"))
    )
    (net (code "15") (name "Net-(CON1C-S)") (class "Default")
      (node (ref "CON1") (pin "P$3") (pinfunction "S_P$3") (pintype "passive"))
      (node (ref "CON2") (pin "P$3") (pinfunction "S_P$3") (pintype "passive"))
      (node (ref "U12") (pin "7") (pinfunction "CANH_7") (pintype "bidirectional"))
    )
    (net (code "16") (name "Net-(D1-A)") (class "Default")
      (node (ref "D1") (pin "2") (pinfunction "A_2") (pintype "passive"))
      (node (ref "Q1") (pin "P$4") (pinfunction "G_P$4") (pintype "passive"))
      (node (ref "R3") (pin "1") (pinfunction "1_1") (pintype "passive"))
      (node (ref "U1") (pin "COLLECTOR") (pinfunction "COL_COLLECTOR") (pintype "passive"))
    )
    (net (code "17") (name "Net-(D2-A)") (class "Default")
      (node (ref "D2") (pin "2") (pinfunction "A_2") (pintype "passive"))
      (node (ref "Q2") (pin "P$4") (pinfunction "G_P$4") (pintype "passive"))
      (node (ref "R9") (pin "1") (pinfunction "1_1") (pintype "passive"))
      (node (ref "U4") (pin "COLLECTOR") (pinfunction "COL_COLLECTOR") (pintype "passive"))
    )
    (net (code "18") (name "Net-(D3-A)") (class "Default")
      (node (ref "D3") (pin "2") (pinfunction "A_2") (pintype "passive"))
      (node (ref "Q3") (pin "P$4") (pinfunction "G_P$4") (pintype "passive"))
      (node (ref "R15") (pin "1") (pinfunction "1_1") (pintype "passive"))
      (node (ref "U7") (pin "COLLECTOR") (pinfunction "COL_COLLECTOR") (pintype "passive"))
    )
    (net (code "19") (name "Net-(D8-PadA)") (class "Default")
      (node (ref "D8") (pin "A") (pinfunction "A_A") (pintype "passive"))
      (node (ref "F6") (pin "1") (pinfunction "1_1") (pintype "passive"))
      (node (ref "R38") (pin "2") (pinfunction "2_2") (pintype "passive"))
    )
    (net (code "20") (name "Net-(F4-2-PadP$3)") (class "Default")
      (node (ref "F4") (pin "P$3") (pinfunction "2_P$3") (pintype "passive"))
      (node (ref "F4") (pin "P$4") (pinfunction "2_P$4") (pintype "passive"))
      (node (ref "V2") (pin "P$1") (pinfunction "1_P$1") (pintype "passive"))
      (node (ref "V2") (pin "P$3") (pinfunction "1_P$3") (pintype "passive"))
    )
    (net (code "21") (name "Net-(F5-2-PadP$3)") (class "Default")
      (node (ref "F5") (pin "P$3") (pinfunction "2_P$3") (pintype "passive"))
      (node (ref "F5") (pin "P$4") (pinfunction "2_P$4") (pintype "passive"))
      (node (ref "V1") (pin "P$1") (pinfunction "1_P$1") (pintype "passive"))
      (node (ref "V1") (pin "P$3") (pinfunction "1_P$3") (pintype "passive"))
    )
    (net (code "22") (name "Net-(JP1-Pad2)") (class "Default")
      (node (ref "JP1") (pin "2") (pinfunction "2_2") (pintype "passive"))
      (node (ref "R28") (pin "1") (pinfunction "1_1") (pintype "passive"))
    )
    (net (code "23") (name "Net-(JP1-Pad4)") (class "Default")
      (node (ref "JP1") (pin "4") (pinfunction "4_4") (pintype "passive"))
      (node (ref "R29") (pin "1") (pinfunction "1_1") (pintype "passive"))
    )
    (net (code "24") (name "Net-(JP1-Pad6)") (class "Default")
      (node (ref "JP1") (pin "6") (pinfunction "6_6") (pintype "passive"))
      (node (ref "JP2") (pin "7") (pinfunction "7_7") (pintype "passive"))
      (node (ref "JP2") (pin "8") (pinfunction "8_8") (pintype "passive"))
    )
    (net (code "25") (name "Net-(LED1-PadA)") (class "Default")
      (node (ref "LED1") (pin "A") (pinfunction "A_A") (pintype "passive"))
      (node (ref "R30") (pin "1") (pinfunction "1_1") (pintype "passive"))
    )
    (net (code "26") (name "Net-(LED2-PadA)") (class "Default")
      (node (ref "LED2") (pin "A") (pinfunction "A_A") (pintype "passive"))
      (node (ref "R33") (pin "1") (pinfunction "1_1") (pintype "passive"))
    )
    (net (code "27") (name "Net-(Q8-G)") (class "Default")
      (node (ref "Q8") (pin "1") (pinfunction "G_1") (pintype "passive"))
      (node (ref "U11") (pin "2") (pinfunction "2_2") (pintype "bidirectional"))
    )
    (net (code "28") (name "Net-(U1-A)") (class "Default")
      (node (ref "R1") (pin "1") (pinfunction "1_1") (pintype "passive"))
      (node (ref "U1") (pin "ANODE") (pinfunction "A_ANODE") (pintype "passive"))
    )
    (net (code "29") (name "Net-(U1-EMIT)") (class "Default")
      (node (ref "R2") (pin "2") (pinfunction "2_2") (pintype "passive"))
      (node (ref "U1") (pin "EMITTER") (pinfunction "EMIT_EMITTER") (pintype "passive"))
    )
    (net (code "30") (name "Net-(U3-A)") (class "Default")
      (node (ref "R5") (pin "1") (pinfunction "1_1") (pintype "passive"))
      (node (ref "U3") (pin "ANODE") (pinfunction "A_ANODE") (pintype "passive"))
    )
    (net (code "31") (name "Net-(U4-A)") (class "Default")
      (node (ref "R7") (pin "1") (pinfunction "1_1") (pintype "passive"))
      (node (ref "U4") (pin "ANODE") (pinfunction "A_ANODE") (pintype "passive"))
    )
    (net (code "32") (name "Net-(U4-EMIT)") (class "Default")
      (node (ref "R8") (pin "2") (pinfunction "2_2") (pintype "passive"))
      (node (ref "U4") (pin "EMITTER") (pinfunction "EMIT_EMITTER") (pintype "passive"))
    )
    (net (code "33") (name "Net-(U6-A)") (class "Default")
      (node (ref "R11") (pin "1") (pinfunction "1_1") (pintype "passive"))
      (node (ref "U6") (pin "ANODE") (pinfunction "A_ANODE") (pintype "passive"))
    )
    (net (code "34") (name "Net-(U7-A)") (class "Default")
      (node (ref "R13") (pin "1") (pinfunction "1_1") (pintype "passive"))
      (node (ref "U7") (pin "ANODE") (pinfunction "A_ANODE") (pintype "passive"))
    )
    (net (code "35") (name "Net-(U7-EMIT)") (class "Default")
      (node (ref "R14") (pin "2") (pinfunction "2_2") (pintype "passive"))
      (node (ref "U7") (pin "EMITTER") (pinfunction "EMIT_EMITTER") (pintype "passive"))
    )
    (net (code "36") (name "Net-(U9-A)") (class "Default")
      (node (ref "R17") (pin "1") (pinfunction "1_1") (pintype "passive"))
      (node (ref "U9") (pin "ANODE") (pinfunction "A_ANODE") (pintype "passive"))
    )
    (net (code "37") (name "Net-(U10-HYS)") (class "Default")
      (node (ref "R26") (pin "1") (pinfunction "1_1") (pintype "passive"))
      (node (ref "U10") (pin "20") (pinfunction "HYS_20") (pintype "bidirectional"))
    )
    (net (code "38") (name "Net-(U10-TMR)") (class "Default")
      (node (ref "C4") (pin "2") (pinfunction "2_2") (pintype "passive"))
      (node (ref "R37") (pin "2") (pinfunction "2_2") (pintype "passive"))
      (node (ref "U10") (pin "1") (pinfunction "TMR_1") (pintype "bidirectional"))
    )
    (net (code "39") (name "Net-(U12-RXD)") (class "Default")
      (node (ref "R32") (pin "2") (pinfunction "2_2") (pintype "passive"))
      (node (ref "U12") (pin "4") (pinfunction "RXD_4") (pintype "bidirectional"))
    )
    (net (code "40") (name "Net-(U12-STB)") (class "Default")
      (node (ref "R34") (pin "2") (pinfunction "2_2") (pintype "passive"))
      (node (ref "U12") (pin "8") (pinfunction "STB_8") (pintype "bidirectional"))
    )
    (net (code "41") (name "Net-(U12-TXD)") (class "Default")
      (node (ref "R31") (pin "2") (pinfunction "2_2") (pintype "passive"))
      (node (ref "U12") (pin "1") (pinfunction "TXD_1") (pintype "bidirectional"))
    )
    (net (code "42") (name "Net-(U13-VIN)") (class "Default")
      (node (ref "D8") (pin "C") (pinfunction "C_C") (pintype "passive"))
      (node (ref "U13") (pin "1") (pinfunction "VIN_1") (pintype "passive"))
    )
    (net (code "43") (name "OV1") (class "Default")
      (node (ref "R20") (pin "1") (pinfunction "1_1") (pintype "passive"))
      (node (ref "R21") (pin "2") (pinfunction "2_2") (pintype "passive"))
      (node (ref "U10") (pin "3") (pinfunction "OV1_3") (pintype "bidirectional"))
    )
    (net (code "44") (name "OV2") (class "Default")
      (node (ref "R23") (pin "1") (pinfunction "1_1") (pintype "passive"))
      (node (ref "R24") (pin "2") (pinfunction "2_2") (pintype "passive"))
      (node (ref "U10") (pin "5") (pinfunction "OV2_5") (pintype "bidirectional"))
    )
    (net (code "45") (name "PGOOD1") (class "Default")
      (node (ref "R6") (pin "1") (pinfunction "1_1") (pintype "passive"))
      (node (ref "U11") (pin "8") (pinfunction "8/TX3_8") (pintype "bidirectional"))
      (node (ref "X2") (pin "P$25") (pinfunction "P$25_P$25") (pintype "bidirectional"))
      (node (ref "X2") (pin "P$26") (pinfunction "P$26_P$26") (pintype "bidirectional"))
    )
    (net (code "46") (name "PGOOD2") (class "Default")
      (node (ref "R12") (pin "1") (pinfunction "1_1") (pintype "passive"))
      (node (ref "U11") (pin "10") (pinfunction "10/TX2/PWM_10") (pintype "bidirectional"))
      (node (ref "X2") (pin "P$19") (pinfunction "P$19_P$19") (pintype "bidirectional"))
      (node (ref "X2") (pin "P$20") (pinfunction "P$20_P$20") (pintype "bidirectional"))
      (node (ref "X4") (pin "P$25") (pinfunction "P$25_P$25") (pintype "bidirectional"))
      (node (ref "X4") (pin "P$26") (pinfunction "P$26_P$26") (pintype "bidirectional"))
    )
    (net (code "47") (name "PGOOD3") (class "Default")
      (node (ref "R18") (pin "1") (pinfunction "1_1") (pintype "passive"))
      (node (ref "U11") (pin "12") (pinfunction "12/MISO_12") (pintype "bidirectional"))
      (node (ref "X2") (pin "P$15") (pinfunction "P$15_P$15") (pintype "bidirectional"))
      (node (ref "X2") (pin "P$16") (pinfunction "P$16_P$16") (pintype "bidirectional"))
      (node (ref "X4") (pin "P$15") (pinfunction "P$15_P$15") (pintype "bidirectional"))
      (node (ref "X4") (pin "P$16") (pinfunction "P$16_P$16") (pintype "bidirectional"))
      (node (ref "X6") (pin "P$25") (pinfunction "P$25_P$25") (pintype "bidirectional"))
      (node (ref "X6") (pin "P$26") (pinfunction "P$26_P$26") (pintype "bidirectional"))
    )
    (net (code "48") (name "RUN1") (class "Default")
      (node (ref "U3") (pin "COLLECTOR") (pinfunction "COL_COLLECTOR") (pintype "passive"))
      (node (ref "X2") (pin "P$23") (pinfunction "P$23_P$23") (pintype "bidirectional"))
      (node (ref "X2") (pin "P$24") (pinfunction "P$24_P$24") (pintype "bidirectional"))
    )
    (net (code "49") (name "RUN2") (class "Default")
      (node (ref "U6") (pin "COLLECTOR") (pinfunction "COL_COLLECTOR") (pintype "passive"))
      (node (ref "X4") (pin "P$23") (pinfunction "P$23_P$23") (pintype "bidirectional"))
      (node (ref "X4") (pin "P$24") (pinfunction "P$24_P$24") (pintype "bidirectional"))
    )
    (net (code "50") (name "RUN3") (class "Default")
      (node (ref "U9") (pin "COLLECTOR") (pinfunction "COL_COLLECTOR") (pintype "passive"))
      (node (ref "X6") (pin "P$23") (pinfunction "P$23_P$23") (pintype "bidirectional"))
      (node (ref "X6") (pin "P$24") (pinfunction "P$24_P$24") (pintype "bidirectional"))
    )
    (net (code "51") (name "SCL") (class "Default")
      (node (ref "JP2") (pin "5") (pinfunction "5_5") (pintype "passive"))
      (node (ref "JP2") (pin "6") (pinfunction "6_6") (pintype "passive"))
      (node (ref "R28") (pin "2") (pinfunction "2_2") (pintype "passive"))
      (node (ref "U11") (pin "19/A5") (pinfunction "19/A5/T/SCL0_19/A5") (pintype "bidirectional"))
      (node (ref "U2") (pin "5") (pinfunction "SCL_5") (pintype "bidirectional"))
      (node (ref "U5") (pin "5") (pinfunction "SCL_5") (pintype "bidirectional"))
      (node (ref "U8") (pin "5") (pinfunction "SCL_5") (pintype "bidirectional"))
      (node (ref "X2") (pin "P$27") (pinfunction "P$27_P$27") (pintype "bidirectional"))
      (node (ref "X2") (pin "P$28") (pinfunction "P$28_P$28") (pintype "bidirectional"))
      (node (ref "X4") (pin "P$27") (pinfunction "P$27_P$27") (pintype "bidirectional"))
      (node (ref "X4") (pin "P$28") (pinfunction "P$28_P$28") (pintype "bidirectional"))
      (node (ref "X6") (pin "P$27") (pinfunction "P$27_P$27") (pintype "bidirectional"))
      (node (ref "X6") (pin "P$28") (pinfunction "P$28_P$28") (pintype "bidirectional"))
    )
    (net (code "52") (name "SDA") (class "Default")
      (node (ref "JP2") (pin "3") (pinfunction "3_3") (pintype "passive"))
      (node (ref "JP2") (pin "4") (pinfunction "4_4") (pintype "passive"))
      (node (ref "R29") (pin "2") (pinfunction "2_2") (pintype "passive"))
      (node (ref "U11") (pin "18/A4") (pinfunction "18/A4/T/SDA0_18/A4") (pintype "bidirectional"))
      (node (ref "U2") (pin "4") (pinfunction "SDA_4") (pintype "bidirectional"))
      (node (ref "U5") (pin "4") (pinfunction "SDA_4") (pintype "bidirectional"))
      (node (ref "U8") (pin "2") (pinfunction "A0_2") (pintype "bidirectional"))
      (node (ref "U8") (pin "4") (pinfunction "SDA_4") (pintype "bidirectional"))
      (node (ref "X2") (pin "P$29") (pinfunction "P$29_P$29") (pintype "bidirectional"))
      (node (ref "X2") (pin "P$30") (pinfunction "P$30_P$30") (pintype "bidirectional"))
      (node (ref "X4") (pin "P$29") (pinfunction "P$29_P$29") (pintype "bidirectional"))
      (node (ref "X4") (pin "P$30") (pinfunction "P$30_P$30") (pintype "bidirectional"))
      (node (ref "X6") (pin "P$29") (pinfunction "P$29_P$29") (pintype "bidirectional"))
      (node (ref "X6") (pin "P$30") (pinfunction "P$30_P$30") (pintype "bidirectional"))
    )
    (net (code "53") (name "UV1") (class "Default")
      (node (ref "R19") (pin "1") (pinfunction "1_1") (pintype "passive"))
      (node (ref "R20") (pin "2") (pinfunction "2_2") (pintype "passive"))
      (node (ref "U10") (pin "2") (pinfunction "UV1_2") (pintype "bidirectional"))
    )
    (net (code "54") (name "UV2") (class "Default")
      (node (ref "R22") (pin "1") (pinfunction "1_1") (pintype "passive"))
      (node (ref "R23") (pin "2") (pinfunction "2_2") (pintype "passive"))
      (node (ref "U10") (pin "4") (pinfunction "UV2_4") (pintype "bidirectional"))
    )
    (net (code "55") (name "V1") (class "Default")
      (node (ref "D5") (pin "C") (pinfunction "1_C") (pintype "passive"))
      (node (ref "F5") (pin "P$1") (pinfunction "1_P$1") (pintype "passive"))
      (node (ref "F5") (pin "P$2") (pinfunction "1_P$2") (pintype "passive"))
      (node (ref "Q6") (pin "5") (pinfunction "D_5") (pintype "passive"))
      (node (ref "Q6") (pin "6") (pinfunction "D_6") (pintype "passive"))
      (node (ref "Q6") (pin "7") (pinfunction "D_7") (pintype "passive"))
      (node (ref "Q6") (pin "8") (pinfunction "D_8") (pintype "passive"))
      (node (ref "Q6") (pin "P$1") (pinfunction "D_P$1") (pintype "passive"))
      (node (ref "R19") (pin "2") (pinfunction "2_2") (pintype "passive"))
      (node (ref "U10") (pin "17") (pinfunction "V1_17") (pintype "bidirectional"))
    )
    (net (code "56") (name "V1_ANALOG_IN") (class "Default")
      (node (ref "R38") (pin "1") (pinfunction "1_1") (pintype "passive"))
      (node (ref "R39") (pin "2") (pinfunction "2_2") (pintype "passive"))
      (node (ref "U11") (pin "17/A3") (pinfunction "17/A3/T_17/A3") (pintype "bidirectional"))
    )
    (net (code "57") (name "V2") (class "Default")
      (node (ref "D4") (pin "C") (pinfunction "1_C") (pintype "passive"))
      (node (ref "F4") (pin "P$1") (pinfunction "1_P$1") (pintype "passive"))
      (node (ref "F4") (pin "P$2") (pinfunction "1_P$2") (pintype "passive"))
      (node (ref "Q4") (pin "5") (pinfunction "D_5") (pintype "passive"))
      (node (ref "Q4") (pin "6") (pinfunction "D_6") (pintype "passive"))
      (node (ref "Q4") (pin "7") (pinfunction "D_7") (pintype "passive"))
      (node (ref "Q4") (pin "8") (pinfunction "D_8") (pintype "passive"))
      (node (ref "Q4") (pin "P$1") (pinfunction "D_P$1") (pintype "passive"))
      (node (ref "R22") (pin "2") (pinfunction "2_2") (pintype "passive"))
      (node (ref "U10") (pin "16") (pinfunction "V2_16") (pintype "bidirectional"))
    )
    (net (code "58") (name "VIN") (class "Default")
      (node (ref "C10") (pin "1") (pinfunction "1_1") (pintype "passive"))
      (node (ref "C6") (pin "+") (pinfunction "+_+") (pintype "passive"))
      (node (ref "C9") (pin "1") (pinfunction "1_1") (pintype "passive"))
      (node (ref "F1") (pin "P$1") (pinfunction "1_P$1") (pintype "passive"))
      (node (ref "F1") (pin "P$2") (pinfunction "1_P$2") (pintype "passive"))
      (node (ref "F2") (pin "P$1") (pinfunction "1_P$1") (pintype "passive"))
      (node (ref "F2") (pin "P$2") (pinfunction "1_P$2") (pintype "passive"))
      (node (ref "F3") (pin "P$1") (pinfunction "1_P$1") (pintype "passive"))
      (node (ref "F3") (pin "P$2") (pinfunction "1_P$2") (pintype "passive"))
      (node (ref "F6") (pin "2") (pinfunction "2_2") (pintype "passive"))
      (node (ref "Q5") (pin "5") (pinfunction "D_5") (pintype "passive"))
      (node (ref "Q5") (pin "6") (pinfunction "D_6") (pintype "passive"))
      (node (ref "Q5") (pin "7") (pinfunction "D_7") (pintype "passive"))
      (node (ref "Q5") (pin "8") (pinfunction "D_8") (pintype "passive"))
      (node (ref "Q5") (pin "P$1") (pinfunction "D_P$1") (pintype "passive"))
      (node (ref "Q7") (pin "5") (pinfunction "D_5") (pintype "passive"))
      (node (ref "Q7") (pin "6") (pinfunction "D_6") (pintype "passive"))
      (node (ref "Q7") (pin "7") (pinfunction "D_7") (pintype "passive"))
      (node (ref "Q7") (pin "8") (pinfunction "D_8") (pintype "passive"))
      (node (ref "Q7") (pin "P$1") (pinfunction "D_P$1") (pintype "passive"))
      (node (ref "U10") (pin "15") (pinfunction "VOUT_15") (pintype "bidirectional"))
    )
    (net (code "59") (name "VIN1") (class "Default")
      (node (ref "F1") (pin "P$3") (pinfunction "2_P$3") (pintype "passive"))
      (node (ref "F1") (pin "P$4") (pinfunction "2_P$4") (pintype "passive"))
      (node (ref "X2") (pin "P$1_1") (pinfunction "P$1_P$1_1") (pintype "bidirectional"))
      (node (ref "X2") (pin "P$1_2") (pinfunction "P$1_P$1_2") (pintype "bidirectional"))
      (node (ref "X2") (pin "P$1_3") (pinfunction "P$1_P$1_3") (pintype "bidirectional"))
      (node (ref "X2") (pin "P$2_1") (pinfunction "P$2_P$2_1") (pintype "bidirectional"))
      (node (ref "X2") (pin "P$2_2") (pinfunction "P$2_P$2_2") (pintype "bidirectional"))
      (node (ref "X2") (pin "P$2_3") (pinfunction "P$2_P$2_3") (pintype "bidirectional"))
    )
    (net (code "60") (name "VIN2") (class "Default")
      (node (ref "F2") (pin "P$3") (pinfunction "2_P$3") (pintype "passive"))
      (node (ref "F2") (pin "P$4") (pinfunction "2_P$4") (pintype "passive"))
      (node (ref "X4") (pin "P$1_1") (pinfunction "P$1_P$1_1") (pintype "bidirectional"))
      (node (ref "X4") (pin "P$1_2") (pinfunction "P$1_P$1_2") (pintype "bidirectional"))
      (node (ref "X4") (pin "P$1_3") (pinfunction "P$1_P$1_3") (pintype "bidirectional"))
      (node (ref "X4") (pin "P$2_1") (pinfunction "P$2_P$2_1") (pintype "bidirectional"))
      (node (ref "X4") (pin "P$2_2") (pinfunction "P$2_P$2_2") (pintype "bidirectional"))
      (node (ref "X4") (pin "P$2_3") (pinfunction "P$2_P$2_3") (pintype "bidirectional"))
    )
    (net (code "61") (name "VIN3") (class "Default")
      (node (ref "F3") (pin "P$3") (pinfunction "2_P$3") (pintype "passive"))
      (node (ref "F3") (pin "P$4") (pinfunction "2_P$4") (pintype "passive"))
      (node (ref "X6") (pin "P$1_1") (pinfunction "P$1_P$1_1") (pintype "bidirectional"))
      (node (ref "X6") (pin "P$1_2") (pinfunction "P$1_P$1_2") (pintype "bidirectional"))
      (node (ref "X6") (pin "P$1_3") (pinfunction "P$1_P$1_3") (pintype "bidirectional"))
      (node (ref "X6") (pin "P$2_1") (pinfunction "P$2_P$2_1") (pintype "bidirectional"))
      (node (ref "X6") (pin "P$2_2") (pinfunction "P$2_P$2_2") (pintype "bidirectional"))
      (node (ref "X6") (pin "P$2_3") (pinfunction "P$2_P$2_3") (pintype "bidirectional"))
    )
    (net (code "62") (name "VOUT1") (class "Default")
      (node (ref "D1") (pin "1") (pinfunction "C_1") (pintype "passive"))
      (node (ref "Q1") (pin "P$1") (pinfunction "S_P$1") (pintype "passive"))
      (node (ref "Q1") (pin "P$2") (pinfunction "S_P$2") (pintype "passive"))
      (node (ref "Q1") (pin "P$3") (pinfunction "S_P$3") (pintype "passive"))
      (node (ref "R3") (pin "2") (pinfunction "2_2") (pintype "passive"))
      (node (ref "R4") (pin "1") (pinfunction "1_1") (pintype "passive"))
      (node (ref "U2") (pin "8") (pinfunction "VBUS_8") (pintype "bidirectional"))
      (node (ref "U2") (pin "9") (pinfunction "IN-_9") (pintype "bidirectional"))
      (node (ref "X1") (pin "P$5") (pinfunction "1_P$5") (pintype "passive"))
      (node (ref "X1") (pin "P$6") (pinfunction "1_P$6") (pintype "passive"))
    )
    (net (code "63") (name "VOUT2") (class "Default")
      (node (ref "D2") (pin "1") (pinfunction "C_1") (pintype "passive"))
      (node (ref "Q2") (pin "P$1") (pinfunction "S_P$1") (pintype "passive"))
      (node (ref "Q2") (pin "P$2") (pinfunction "S_P$2") (pintype "passive"))
      (node (ref "Q2") (pin "P$3") (pinfunction "S_P$3") (pintype "passive"))
      (node (ref "R10") (pin "1") (pinfunction "1_1") (pintype "passive"))
      (node (ref "R9") (pin "2") (pinfunction "2_2") (pintype "passive"))
      (node (ref "U5") (pin "8") (pinfunction "VBUS_8") (pintype "bidirectional"))
      (node (ref "U5") (pin "9") (pinfunction "IN-_9") (pintype "bidirectional"))
      (node (ref "X3") (pin "P$5") (pinfunction "1_P$5") (pintype "passive"))
      (node (ref "X3") (pin "P$6") (pinfunction "1_P$6") (pintype "passive"))
    )
    (net (code "64") (name "VOUT3") (class "Default")
      (node (ref "D3") (pin "1") (pinfunction "C_1") (pintype "passive"))
      (node (ref "Q3") (pin "P$1") (pinfunction "S_P$1") (pintype "passive"))
      (node (ref "Q3") (pin "P$2") (pinfunction "S_P$2") (pintype "passive"))
      (node (ref "Q3") (pin "P$3") (pinfunction "S_P$3") (pintype "passive"))
      (node (ref "R15") (pin "2") (pinfunction "2_2") (pintype "passive"))
      (node (ref "R16") (pin "1") (pinfunction "1_1") (pintype "passive"))
      (node (ref "U8") (pin "8") (pinfunction "VBUS_8") (pintype "bidirectional"))
      (node (ref "U8") (pin "9") (pinfunction "IN-_9") (pintype "bidirectional"))
      (node (ref "X5") (pin "P$5") (pinfunction "1_P$5") (pintype "passive"))
      (node (ref "X5") (pin "P$6") (pinfunction "1_P$6") (pintype "passive"))
    )
    (net (code "65") (name "VOUT_SENSE1") (class "Default")
      (node (ref "R4") (pin "2") (pinfunction "2_2") (pintype "passive"))
      (node (ref "U2") (pin "10") (pinfunction "IN+_10") (pintype "bidirectional"))
      (node (ref "X2") (pin "P$5_1") (pinfunction "P$5_P$5_1") (pintype "bidirectional"))
      (node (ref "X2") (pin "P$5_2") (pinfunction "P$5_P$5_2") (pintype "bidirectional"))
      (node (ref "X2") (pin "P$5_3") (pinfunction "P$5_P$5_3") (pintype "bidirectional"))
      (node (ref "X2") (pin "P$6_1") (pinfunction "P$6_P$6_1") (pintype "bidirectional"))
      (node (ref "X2") (pin "P$6_2") (pinfunction "P$6_P$6_2") (pintype "bidirectional"))
      (node (ref "X2") (pin "P$6_3") (pinfunction "P$6_P$6_3") (pintype "bidirectional"))
    )
    (net (code "66") (name "VOUT_SENSE2") (class "Default")
      (node (ref "R10") (pin "2") (pinfunction "2_2") (pintype "passive"))
      (node (ref "U5") (pin "10") (pinfunction "IN+_10") (pintype "bidirectional"))
      (node (ref "X4") (pin "P$5_1") (pinfunction "P$5_P$5_1") (pintype "bidirectional"))
      (node (ref "X4") (pin "P$5_2") (pinfunction "P$5_P$5_2") (pintype "bidirectional"))
      (node (ref "X4") (pin "P$5_3") (pinfunction "P$5_P$5_3") (pintype "bidirectional"))
      (node (ref "X4") (pin "P$6_1") (pinfunction "P$6_P$6_1") (pintype "bidirectional"))
      (node (ref "X4") (pin "P$6_2") (pinfunction "P$6_P$6_2") (pintype "bidirectional"))
      (node (ref "X4") (pin "P$6_3") (pinfunction "P$6_P$6_3") (pintype "bidirectional"))
    )
    (net (code "67") (name "VOUT_SENSE3") (class "Default")
      (node (ref "R16") (pin "2") (pinfunction "2_2") (pintype "passive"))
      (node (ref "U8") (pin "10") (pinfunction "IN+_10") (pintype "bidirectional"))
      (node (ref "X6") (pin "P$5_1") (pinfunction "P$5_P$5_1") (pintype "bidirectional"))
      (node (ref "X6") (pin "P$5_2") (pinfunction "P$5_P$5_2") (pintype "bidirectional"))
      (node (ref "X6") (pin "P$5_3") (pinfunction "P$5_P$5_3") (pintype "bidirectional"))
      (node (ref "X6") (pin "P$6_1") (pinfunction "P$6_P$6_1") (pintype "bidirectional"))
      (node (ref "X6") (pin "P$6_2") (pinfunction "P$6_P$6_2") (pintype "bidirectional"))
      (node (ref "X6") (pin "P$6_3") (pinfunction "P$6_P$6_3") (pintype "bidirectional"))
    )
    (net (code "68") (name "VOUT_SWITCHED1") (class "Default")
      (node (ref "Q1") (pin "P$5") (pinfunction "D_P$5") (pintype "passive"))
      (node (ref "Q1") (pin "P$6") (pinfunction "D_P$6") (pintype "passive"))
      (node (ref "Q1") (pin "P$7") (pinfunction "D_P$7") (pintype "passive"))
      (node (ref "Q1") (pin "P$8") (pinfunction "D_P$8") (pintype "passive"))
      (node (ref "X1") (pin "P$4") (pinfunction "1_P$4") (pintype "passive"))
    )
    (net (code "69") (name "VOUT_SWITCHED2") (class "Default")
      (node (ref "Q2") (pin "P$5") (pinfunction "D_P$5") (pintype "passive"))
      (node (ref "Q2") (pin "P$6") (pinfunction "D_P$6") (pintype "passive"))
      (node (ref "Q2") (pin "P$7") (pinfunction "D_P$7") (pintype "passive"))
      (node (ref "Q2") (pin "P$8") (pinfunction "D_P$8") (pintype "passive"))
      (node (ref "X3") (pin "P$4") (pinfunction "1_P$4") (pintype "passive"))
    )
    (net (code "70") (name "VOUT_SWITCHED3") (class "Default")
      (node (ref "Q3") (pin "P$5") (pinfunction "D_P$5") (pintype "passive"))
      (node (ref "Q3") (pin "P$6") (pinfunction "D_P$6") (pintype "passive"))
      (node (ref "Q3") (pin "P$7") (pinfunction "D_P$7") (pintype "passive"))
      (node (ref "Q3") (pin "P$8") (pinfunction "D_P$8") (pintype "passive"))
      (node (ref "X5") (pin "P$4") (pinfunction "1_P$4") (pintype "passive"))
    )
    (net (code "71") (name "VS1") (class "Default")
      (node (ref "Q6") (pin "1") (pinfunction "S_1") (pintype "passive"))
      (node (ref "Q6") (pin "2") (pinfunction "S_2") (pintype "passive"))
      (node (ref "Q6") (pin "3") (pinfunction "S_3") (pintype "passive"))
      (node (ref "Q7") (pin "1") (pinfunction "S_1") (pintype "passive"))
      (node (ref "Q7") (pin "2") (pinfunction "S_2") (pintype "passive"))
      (node (ref "Q7") (pin "3") (pinfunction "S_3") (pintype "passive"))
      (node (ref "U10") (pin "14") (pinfunction "VS1_14") (pintype "bidirectional"))
    )
    (net (code "72") (name "VS2") (class "Default")
      (node (ref "Q4") (pin "1") (pinfunction "S_1") (pintype "passive"))
      (node (ref "Q4") (pin "2") (pinfunction "S_2") (pintype "passive"))
      (node (ref "Q4") (pin "3") (pinfunction "S_3") (pintype "passive"))
      (node (ref "Q5") (pin "1") (pinfunction "S_1") (pintype "passive"))
      (node (ref "Q5") (pin "2") (pinfunction "S_2") (pintype "passive"))
      (node (ref "Q5") (pin "3") (pinfunction "S_3") (pintype "passive"))
      (node (ref "U10") (pin "12") (pinfunction "VS2_12") (pintype "bidirectional"))
    )
    (net (code "73") (name "unconnected-(U2-ALERT-Pad3)") (class "Default")
      (node (ref "U2") (pin "3") (pinfunction "ALERT_3") (pintype "bidirectional"))
    )
    (net (code "74") (name "unconnected-(U5-ALERT-Pad3)") (class "Default")
      (node (ref "U5") (pin "3") (pinfunction "ALERT_3") (pintype "bidirectional"))
    )
    (net (code "75") (name "unconnected-(U8-ALERT-Pad3)") (class "Default")
      (node (ref "U8") (pin "3") (pinfunction "ALERT_3") (pintype "bidirectional"))
    )
    (net (code "76") (name "unconnected-(U10-CAS-Pad9)") (class "Default")
      (node (ref "U10") (pin "9") (pinfunction "CAS_9") (pintype "bidirectional"))
    )
    (net (code "77") (name "unconnected-(U11-0{slash}RX1{slash}T-Pad0)") (class "Default")
      (node (ref "U11") (pin "0") (pinfunction "0/RX1/T_0") (pintype "bidirectional"))
    )
    (net (code "78") (name "unconnected-(U11-1{slash}TX1{slash}T-Pad1)") (class "Default")
      (node (ref "U11") (pin "1") (pinfunction "1/TX1/T_1") (pintype "bidirectional"))
    )
    (net (code "79") (name "unconnected-(U11-5{slash}PWM-Pad5)") (class "Default")
      (node (ref "U11") (pin "5") (pinfunction "5/PWM_5") (pintype "bidirectional"))
    )
    (net (code "80") (name "unconnected-(U11-6{slash}PWM-Pad6)") (class "Default")
      (node (ref "U11") (pin "6") (pinfunction "6/PWM_6") (pintype "bidirectional"))
    )
    (net (code "81") (name "unconnected-(U11-13{slash}SCK{slash}LED-Pad13)") (class "Default")
      (node (ref "U11") (pin "13") (pinfunction "13/SCK/LED_13") (pintype "bidirectional"))
    )
    (net (code "82") (name "unconnected-(U11-16{slash}A2{slash}T-Pad16{slash}A2)") (class "Default")
      (node (ref "U11") (pin "16/A2") (pinfunction "16/A2/T_16/A2") (pintype "bidirectional"))
    )
    (net (code "83") (name "unconnected-(U11-20{slash}A6{slash}PWM-Pad20{slash}A6)") (class "Default")
      (node (ref "U11") (pin "20/A6") (pinfunction "20/A6/PWM_20/A6") (pintype "bidirectional"))
    )
    (net (code "84") (name "unconnected-(U11-21{slash}A7{slash}PWM-Pad21{slash}A7)") (class "Default")
      (node (ref "U11") (pin "21/A7") (pinfunction "21/A7/PWM_21/A7") (pintype "bidirectional"))
    )
    (net (code "85") (name "unconnected-(U11-22{slash}A8{slash}T{slash}PWM-Pad22{slash}A8)") (class "Default")
      (node (ref "U11") (pin "22/A8") (pinfunction "22/A8/T/PWM_22/A8") (pintype "bidirectional"))
    )
    (net (code "86") (name "unconnected-(U11-23{slash}A9{slash}T{slash}PWM-Pad23{slash}A9)") (class "Default")
      (node (ref "U11") (pin "23/A9") (pinfunction "23/A9/T/PWM_23/A9") (pintype "bidirectional"))
    )
    (net (code "87") (name "unconnected-(X2-PadP$7)") (class "Default")
      (node (ref "X2") (pin "P$7") (pinfunction "P$7_P$7") (pintype "bidirectional"))
    )
    (net (code "88") (name "unconnected-(X2-PadP$8)") (class "Default")
      (node (ref "X2") (pin "P$8") (pinfunction "P$8_P$8") (pintype "bidirectional"))
    )
    (net (code "89") (name "unconnected-(X2-PadP$9)") (class "Default")
      (node (ref "X2") (pin "P$9") (pinfunction "P$9_P$9") (pintype "bidirectional"))
    )
    (net (code "90") (name "unconnected-(X2-PadP$10)") (class "Default")
      (node (ref "X2") (pin "P$10") (pinfunction "P$10_P$10") (pintype "bidirectional"))
    )
    (net (code "91") (name "unconnected-(X2-PadP$13)") (class "Default")
      (node (ref "X2") (pin "P$13") (pinfunction "P$13_P$13") (pintype "bidirectional"))
    )
    (net (code "92") (name "unconnected-(X2-PadP$14)") (class "Default")
      (node (ref "X2") (pin "P$14") (pinfunction "P$14_P$14") (pintype "bidirectional"))
    )
    (net (code "93") (name "unconnected-(X4-PadP$7)") (class "Default")
      (node (ref "X4") (pin "P$7") (pinfunction "P$7_P$7") (pintype "bidirectional"))
    )
    (net (code "94") (name "unconnected-(X4-PadP$8)") (class "Default")
      (node (ref "X4") (pin "P$8") (pinfunction "P$8_P$8") (pintype "bidirectional"))
    )
    (net (code "95") (name "unconnected-(X4-PadP$9)") (class "Default")
      (node (ref "X4") (pin "P$9") (pinfunction "P$9_P$9") (pintype "bidirectional"))
    )
    (net (code "96") (name "unconnected-(X4-PadP$10)") (class "Default")
      (node (ref "X4") (pin "P$10") (pinfunction "P$10_P$10") (pintype "bidirectional"))
    )
    (net (code "97") (name "unconnected-(X4-PadP$13)") (class "Default")
      (node (ref "X4") (pin "P$13") (pinfunction "P$13_P$13") (pintype "bidirectional"))
    )
    (net (code "98") (name "unconnected-(X4-PadP$14)") (class "Default")
      (node (ref "X4") (pin "P$14") (pinfunction "P$14_P$14") (pintype "bidirectional"))
    )
    (net (code "99") (name "unconnected-(X4-PadP$19)") (class "Default")
      (node (ref "X4") (pin "P$19") (pinfunction "P$19_P$19") (pintype "bidirectional"))
    )
    (net (code "100") (name "unconnected-(X4-PadP$20)") (class "Default")
      (node (ref "X4") (pin "P$20") (pinfunction "P$20_P$20") (pintype "bidirectional"))
    )
    (net (code "101") (name "unconnected-(X4-PadP$21)") (class "Default")
      (node (ref "X4") (pin "P$21") (pinfunction "P$21_P$21") (pintype "bidirectional"))
    )
    (net (code "102") (name "unconnected-(X4-PadP$22)") (class "Default")
      (node (ref "X4") (pin "P$22") (pinfunction "P$22_P$22") (pintype "bidirectional"))
    )
    (net (code "103") (name "unconnected-(X6-PadP$7)") (class "Default")
      (node (ref "X6") (pin "P$7") (pinfunction "P$7_P$7") (pintype "bidirectional"))
    )
    (net (code "104") (name "unconnected-(X6-PadP$8)") (class "Default")
      (node (ref "X6") (pin "P$8") (pinfunction "P$8_P$8") (pintype "bidirectional"))
    )
    (net (code "105") (name "unconnected-(X6-PadP$9)") (class "Default")
      (node (ref "X6") (pin "P$9") (pinfunction "P$9_P$9") (pintype "bidirectional"))
    )
    (net (code "106") (name "unconnected-(X6-PadP$10)") (class "Default")
      (node (ref "X6") (pin "P$10") (pinfunction "P$10_P$10") (pintype "bidirectional"))
    )
    (net (code "107") (name "unconnected-(X6-PadP$13)") (class "Default")
      (node (ref "X6") (pin "P$13") (pinfunction "P$13_P$13") (pintype "bidirectional"))
    )
    (net (code "108") (name "unconnected-(X6-PadP$14)") (class "Default")
      (node (ref "X6") (pin "P$14") (pinfunction "P$14_P$14") (pintype "bidirectional"))
    )
    (net (code "109") (name "unconnected-(X6-PadP$15)") (class "Default")
      (node (ref "X6") (pin "P$15") (pinfunction "P$15_P$15") (pintype "bidirectional"))
    )
    (net (code "110") (name "unconnected-(X6-PadP$16)") (class "Default")
      (node (ref "X6") (pin "P$16") (pinfunction "P$16_P$16") (pintype "bidirectional"))
    )
    (net (code "111") (name "unconnected-(X6-PadP$17)") (class "Default")
      (node (ref "X6") (pin "P$17") (pinfunction "P$17_P$17") (pintype "bidirectional"))
    )
    (net (code "112") (name "unconnected-(X6-PadP$19)") (class "Default")
      (node (ref "X6") (pin "P$19") (pinfunction "P$19_P$19") (pintype "bidirectional"))
    )
    (net (code "113") (name "unconnected-(X6-PadP$20)") (class "Default")
      (node (ref "X6") (pin "P$20") (pinfunction "P$20_P$20") (pintype "bidirectional"))
    )
    (net (code "114") (name "unconnected-(X6-PadP$21)") (class "Default")
      (node (ref "X6") (pin "P$21") (pinfunction "P$21_P$21") (pintype "bidirectional"))
    )
    (net (code "115") (name "unconnected-(X6-PadP$22)") (class "Default")
      (node (ref "X6") (pin "P$22") (pinfunction "P$22_P$22") (pintype "bidirectional"))
    )
    (net (code "116") (name "{slash}MCU_RUN1") (class "Default")
      (node (ref "R5") (pin "2") (pinfunction "2_2") (pintype "passive"))
      (node (ref "U11") (pin "7") (pinfunction "7/RX3_7") (pintype "bidirectional"))
    )
    (net (code "117") (name "{slash}MCU_RUN2") (class "Default")
      (node (ref "R11") (pin "2") (pinfunction "2_2") (pintype "passive"))
      (node (ref "U11") (pin "9") (pinfunction "9/RX2/PWM_9") (pintype "bidirectional"))
      (node (ref "X2") (pin "P$21") (pinfunction "P$21_P$21") (pintype "bidirectional"))
      (node (ref "X2") (pin "P$22") (pinfunction "P$22_P$22") (pintype "bidirectional"))
    )
    (net (code "118") (name "{slash}MCU_RUN3") (class "Default")
      (node (ref "R17") (pin "2") (pinfunction "2_2") (pintype "passive"))
      (node (ref "U11") (pin "11") (pinfunction "11/MOSI_11") (pintype "bidirectional"))
      (node (ref "X2") (pin "P$17") (pinfunction "P$17_P$17") (pintype "bidirectional"))
      (node (ref "X2") (pin "P$18") (pinfunction "P$18_P$18") (pintype "bidirectional"))
      (node (ref "X4") (pin "P$17") (pinfunction "P$17_P$17") (pintype "bidirectional"))
      (node (ref "X4") (pin "P$18") (pinfunction "P$18_P$18") (pintype "bidirectional"))
      (node (ref "X6") (pin "P$18") (pinfunction "P$18_P$18") (pintype "bidirectional"))
    )
    (net (code "119") (name "{slash}VALID1") (class "Default")
      (node (ref "LED1") (pin "C") (pinfunction "C_C") (pintype "passive"))
      (node (ref "R25") (pin "2") (pinfunction "2_2") (pintype "passive"))
      (node (ref "U10") (pin "6") (pinfunction "/VALID1_6") (pintype "bidirectional"))
      (node (ref "U11") (pin "14/A0") (pinfunction "14/A0_14/A0") (pintype "bidirectional"))
    )
    (net (code "120") (name "{slash}VALID2") (class "Default")
      (node (ref "LED2") (pin "C") (pinfunction "C_C") (pintype "passive"))
      (node (ref "R27") (pin "2") (pinfunction "2_2") (pintype "passive"))
      (node (ref "U10") (pin "7") (pinfunction "/VALID2_7") (pintype "bidirectional"))
      (node (ref "U11") (pin "15/A1") (pinfunction "15/A1/T_15/A1") (pintype "bidirectional"))
    )
  )
)
